# LinTempCont_4ch_V1_0.net
KiCad netlist of a schematic drawn in EAGLE
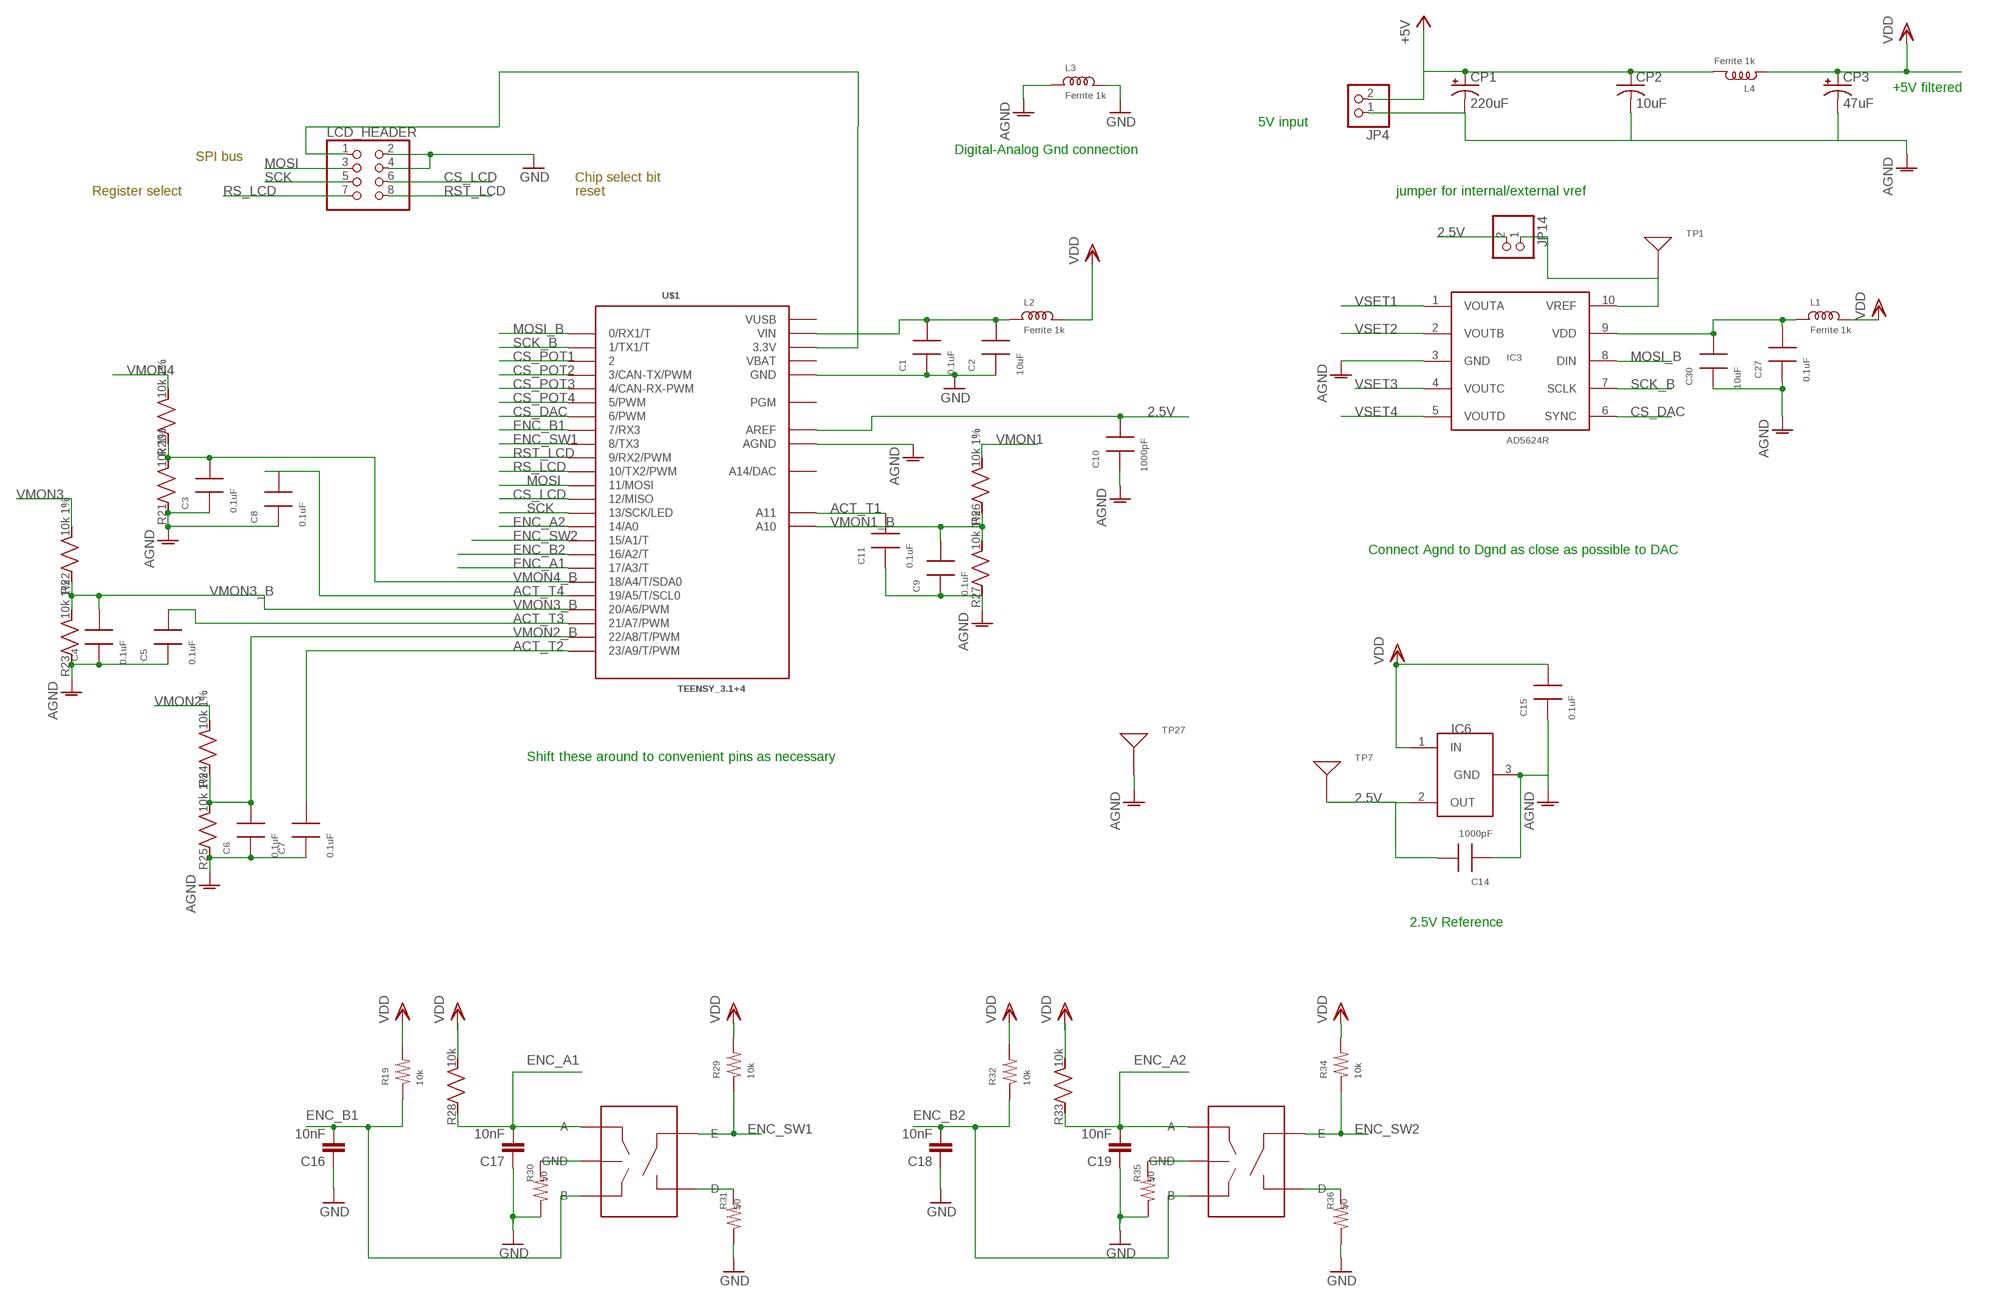
[diagram p0: schematic, sheet 1]
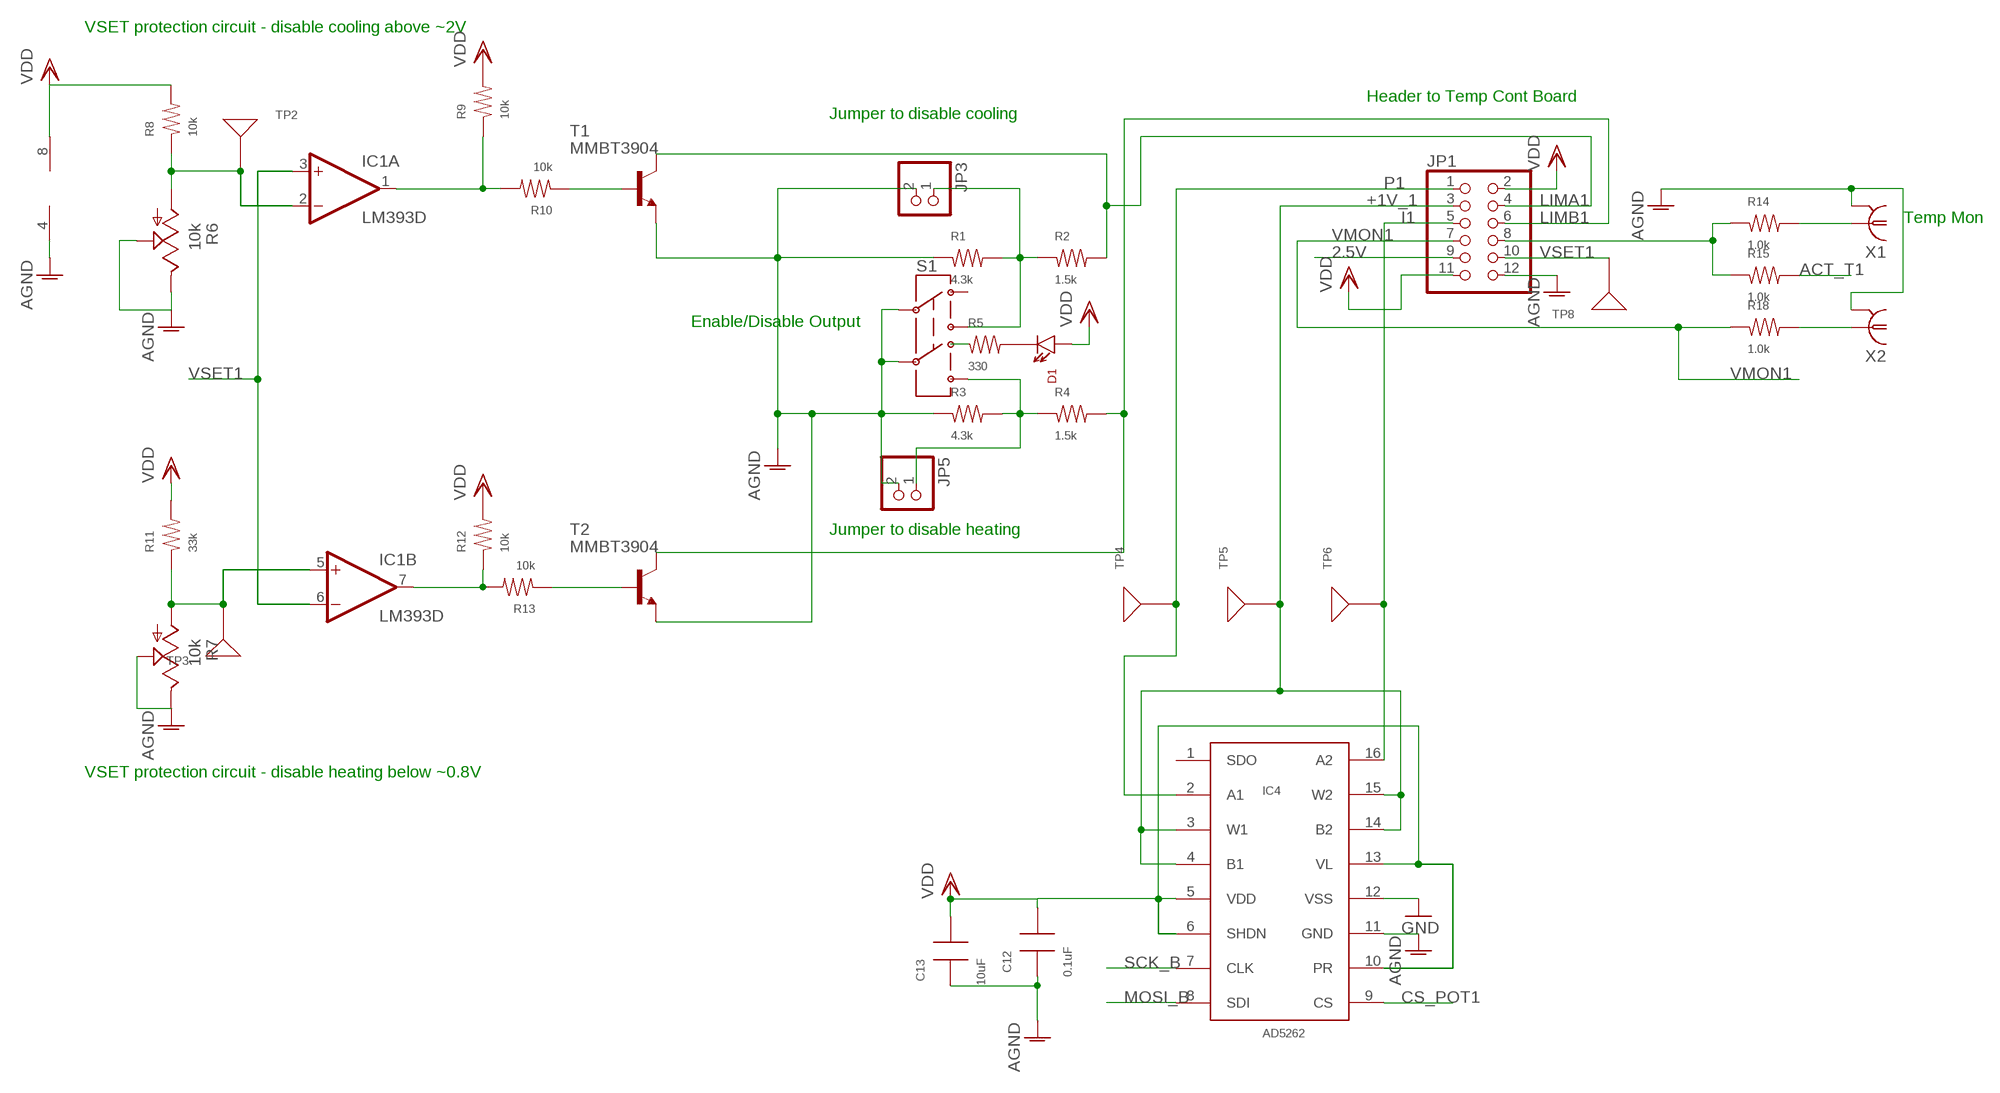
[diagram p1: schematic, sheet 2]
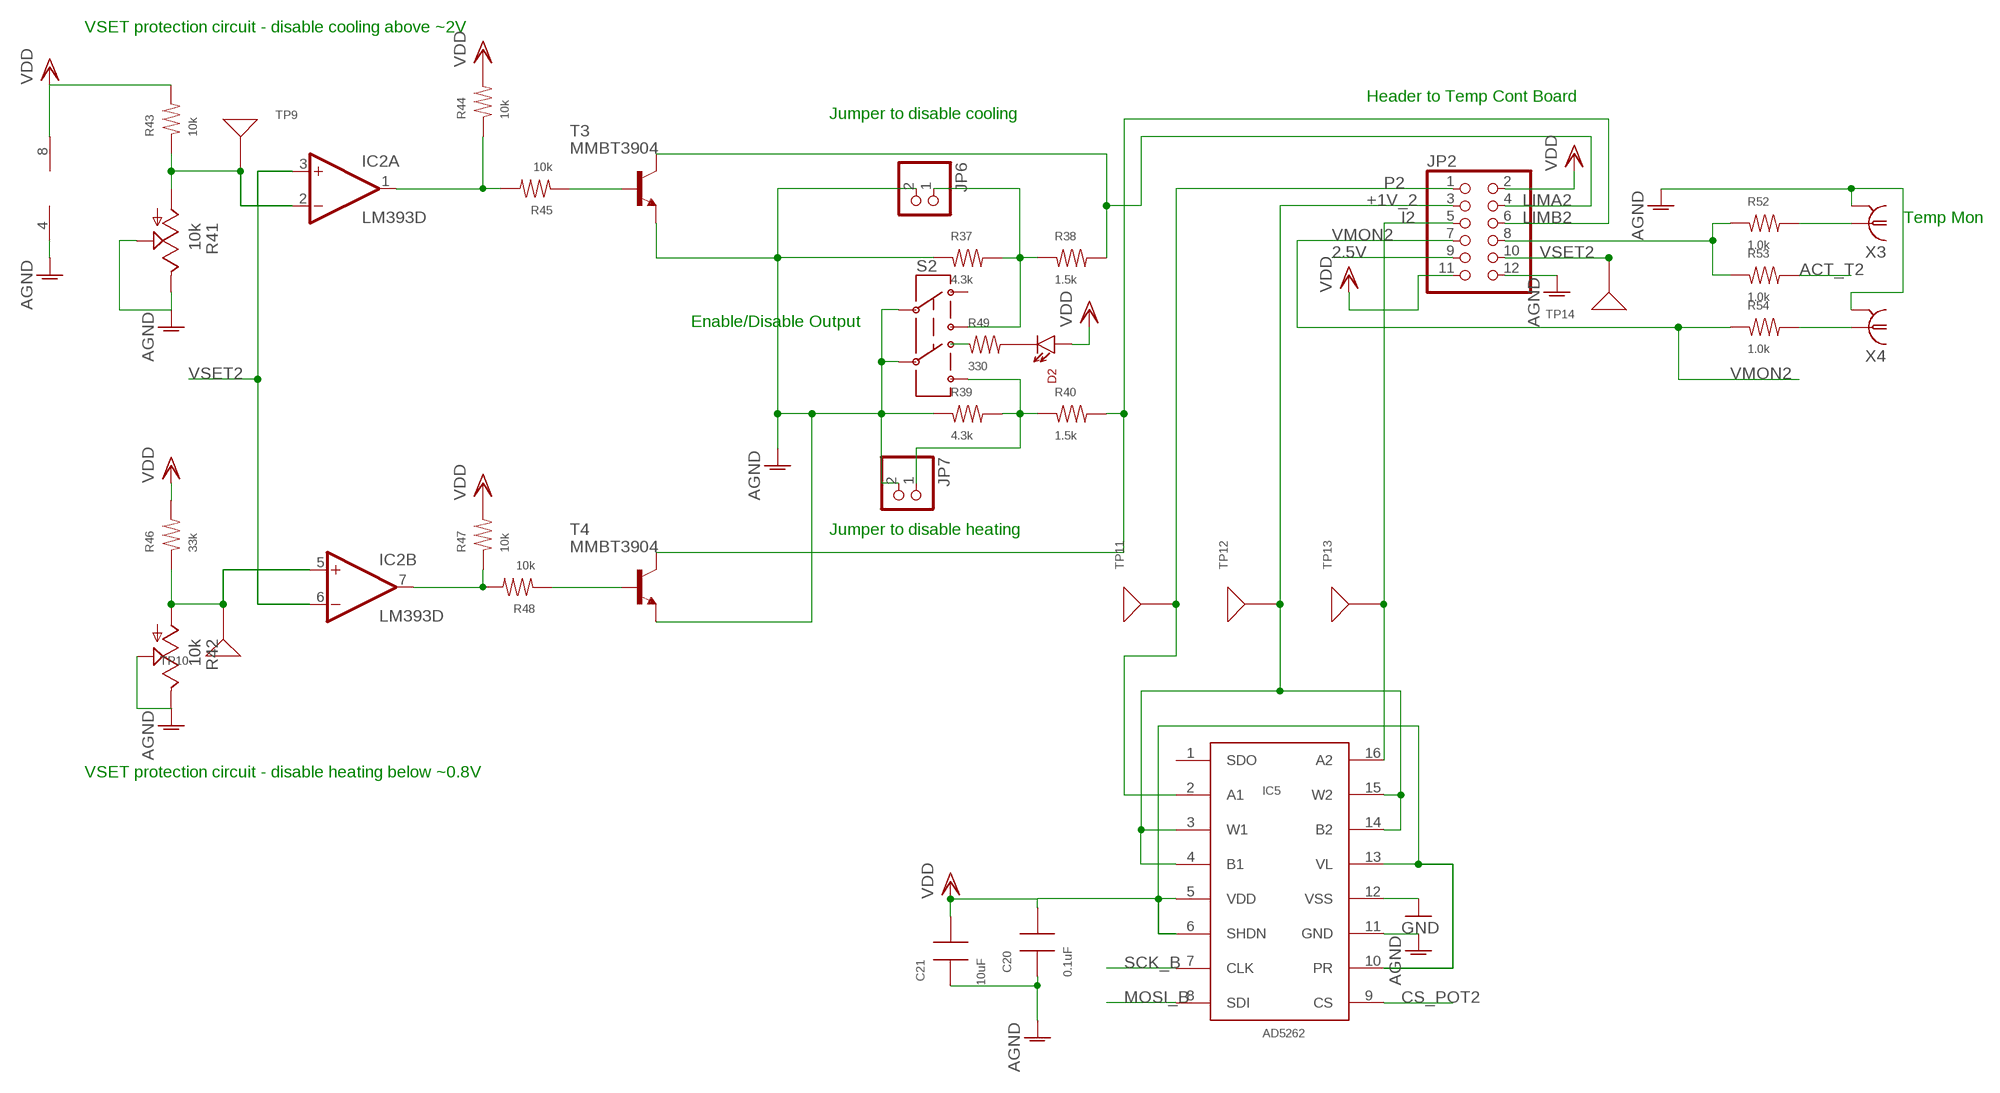
[diagram p2: schematic, sheet 3]
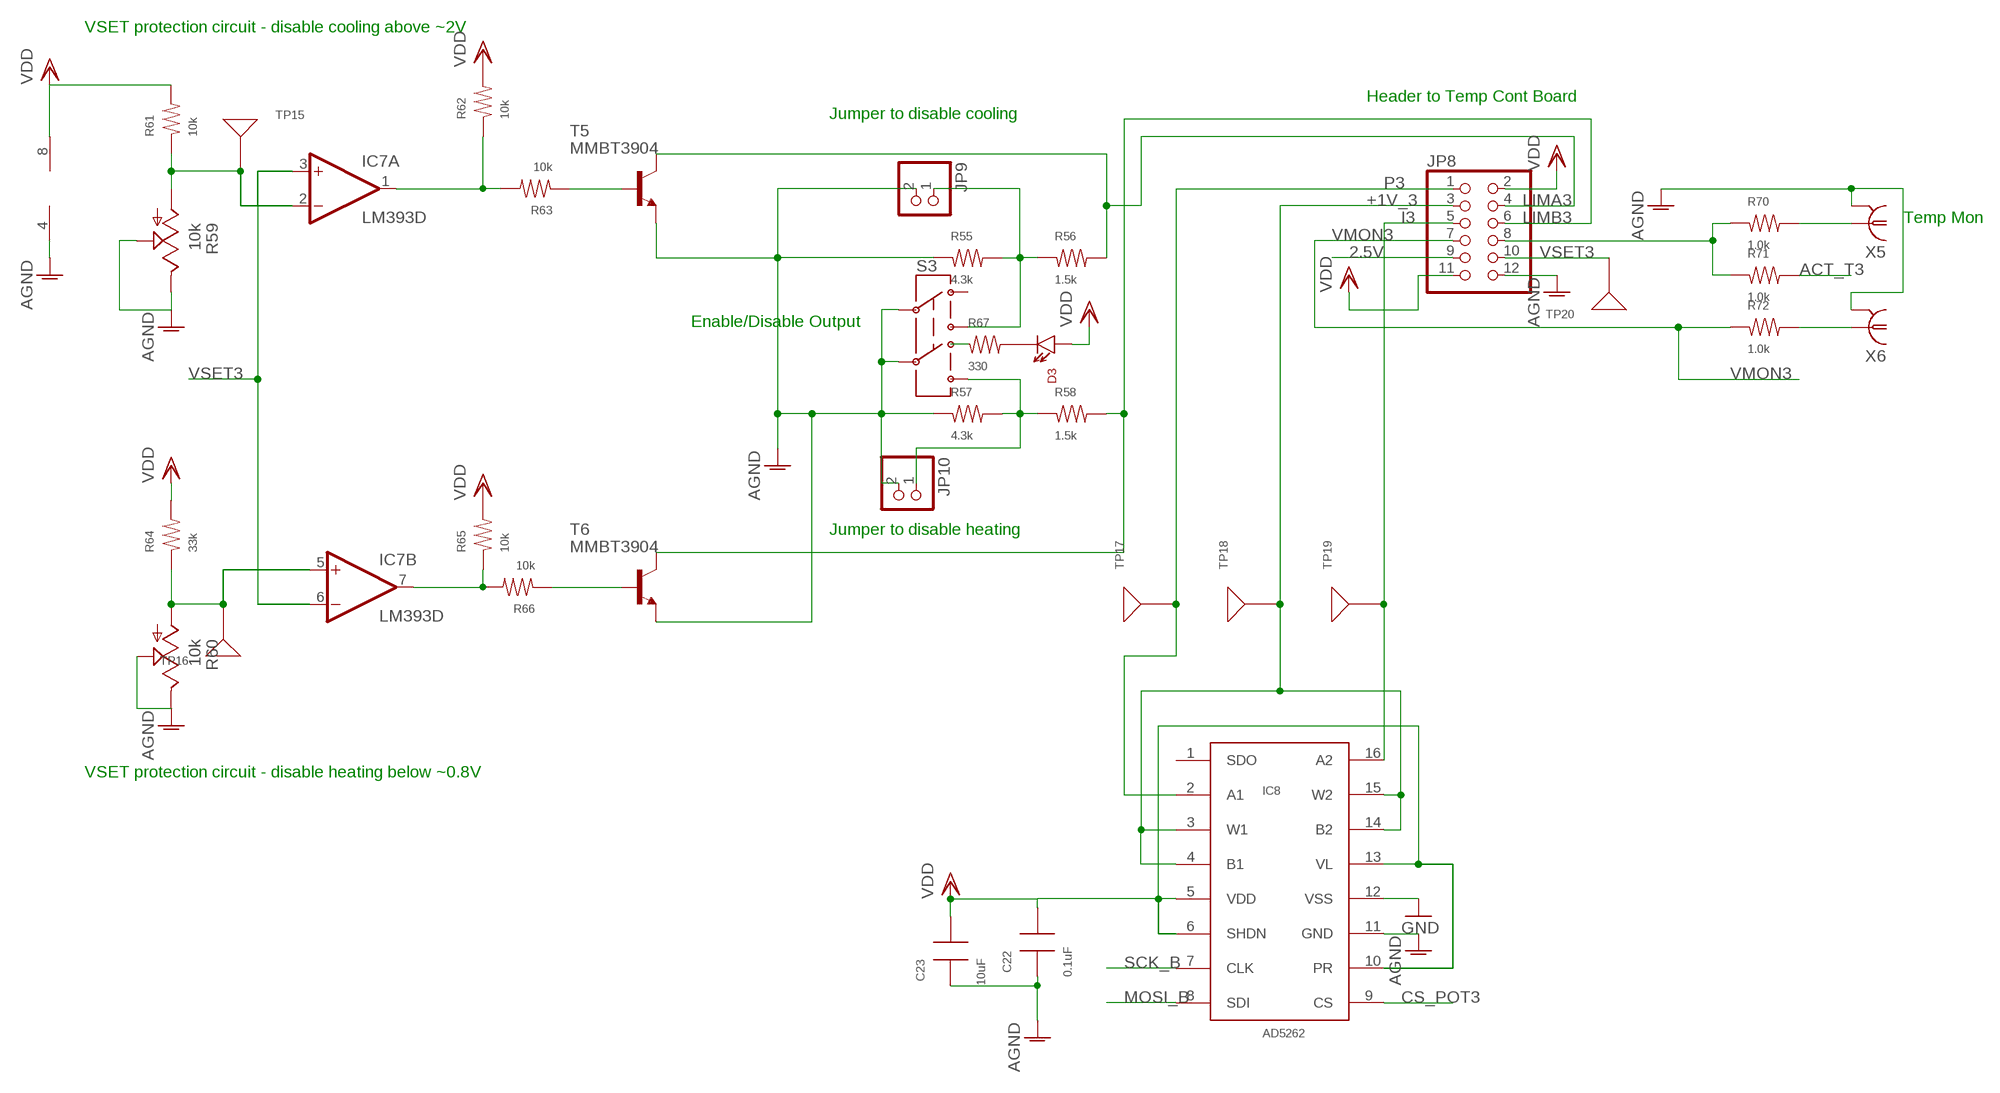
[diagram p3: schematic, sheet 4]
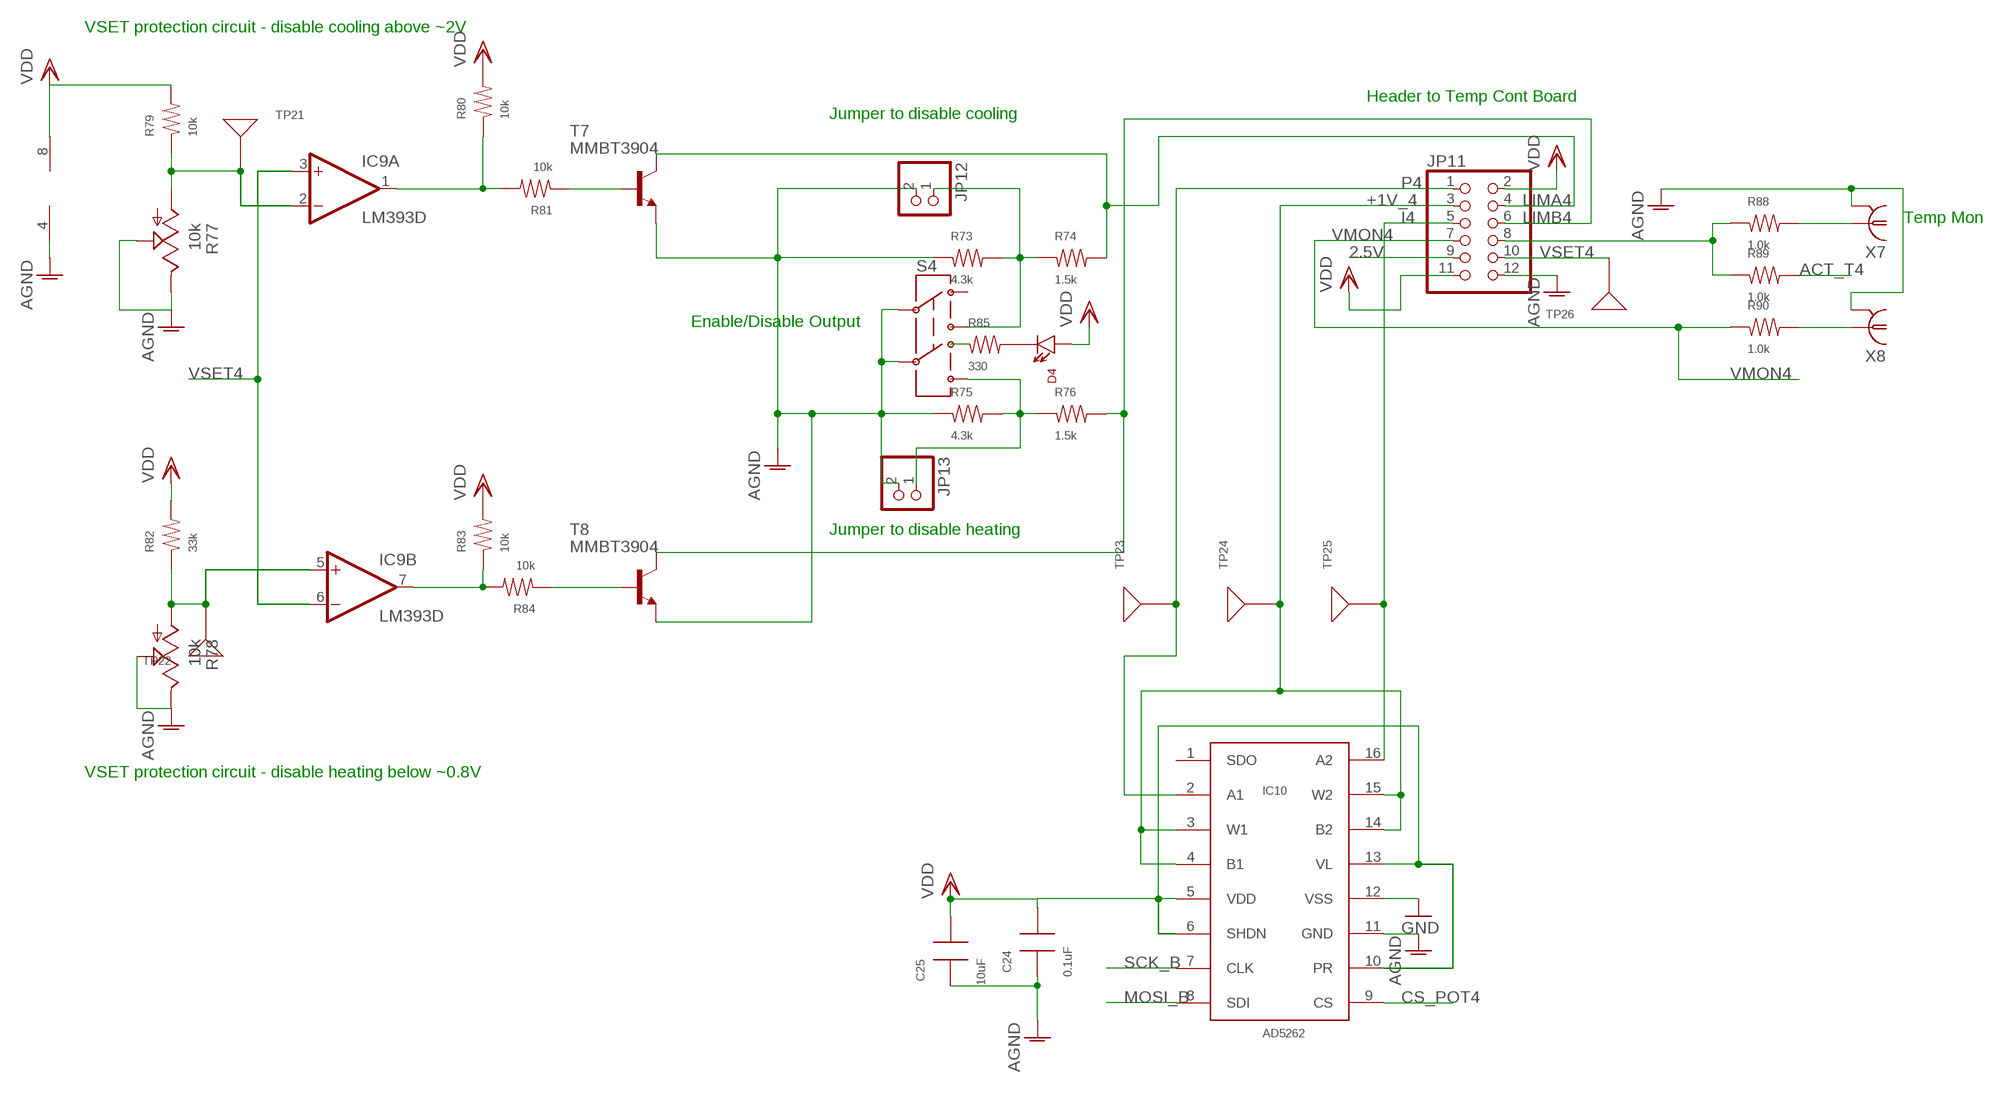
[diagram p4: schematic, sheet 5]

(export (version "E")
  (design (tool "Eeschema 10.0.6"))
  (components
    (comp (ref "C24")
      (value "0.1uF")
      (footprint "eagle-import:0603")
      (libsource (lib "eagle-import") (part "CAP0603"))
    )
    (comp (ref "C25")
      (value "10uF")
      (footprint "eagle-import:0805")
      (libsource (lib "eagle-import") (part "CAP0805"))
    )
    (comp (ref "D4")
      (value "LED/MINI-IND")
      (footprint "eagle-import:HLMP--F0010")
      (libsource (lib "eagle-import") (part "LED/MINI-IND"))
    )
    (comp (ref "IC9")
      (value "LM393D")
      (footprint "eagle-import:SO08")
      (libsource (lib "eagle-import") (part "LM393D"))
    )
    (comp (ref "IC10")
      (value "AD5262")
      (footprint "eagle-import:TSSOP16")
      (libsource (lib "eagle-import") (part "AD5262"))
    )
    (comp (ref "JP11")
      (value "PINHD-2X6/90")
      (footprint "eagle-import:2X06_90")
      (libsource (lib "eagle-import") (part "PINHD-2X6/90"))
    )
    (comp (ref "JP12")
      (value "PINHD-1X2")
      (footprint "eagle-import:1X02")
      (libsource (lib "eagle-import") (part "PINHD-1X2"))
    )
    (comp (ref "JP13")
      (value "PINHD-1X2")
      (footprint "eagle-import:1X02")
      (libsource (lib "eagle-import") (part "PINHD-1X2"))
    )
    (comp (ref "R73")
      (value "4.3k")
      (footprint "eagle-import:0603")
      (libsource (lib "eagle-import") (part "RES0603"))
    )
    (comp (ref "R74")
      (value "1.5k")
      (footprint "eagle-import:0603")
      (libsource (lib "eagle-import") (part "RES0603"))
    )
    (comp (ref "R75")
      (value "4.3k")
      (footprint "eagle-import:0603")
      (libsource (lib "eagle-import") (part "RES0603"))
    )
    (comp (ref "R76")
      (value "1.5k")
      (footprint "eagle-import:0603")
      (libsource (lib "eagle-import") (part "RES0603"))
    )
    (comp (ref "R77")
      (value "10k")
      (footprint "eagle-import:64WPOT")
      (libsource (lib "eagle-import") (part "MODEL64_TRIMPOT/TOP-ADJ"))
    )
    (comp (ref "R78")
      (value "10k")
      (footprint "eagle-import:64WPOT")
      (libsource (lib "eagle-import") (part "MODEL64_TRIMPOT/TOP-ADJ"))
    )
    (comp (ref "R79")
      (value "10k")
      (footprint "eagle-import:0603")
      (libsource (lib "eagle-import") (part "RES0603"))
    )
    (comp (ref "R80")
      (value "10k")
      (footprint "eagle-import:0603")
      (libsource (lib "eagle-import") (part "RES0603"))
    )
    (comp (ref "R81")
      (value "10k")
      (footprint "eagle-import:0603")
      (libsource (lib "eagle-import") (part "RES0603"))
    )
    (comp (ref "R82")
      (value "33k")
      (footprint "eagle-import:0603")
      (libsource (lib "eagle-import") (part "RES0603"))
    )
    (comp (ref "R83")
      (value "10k")
      (footprint "eagle-import:0603")
      (libsource (lib "eagle-import") (part "RES0603"))
    )
    (comp (ref "R84")
      (value "10k")
      (footprint "eagle-import:0603")
      (libsource (lib "eagle-import") (part "RES0603"))
    )
    (comp (ref "R85")
      (value "330")
      (footprint "eagle-import:0603")
      (libsource (lib "eagle-import") (part "RES0603"))
    )
    (comp (ref "R88")
      (value "1.0k")
      (footprint "eagle-import:0603")
      (libsource (lib "eagle-import") (part "RES0603"))
    )
    (comp (ref "R89")
      (value "1.0k")
      (footprint "eagle-import:0603")
      (libsource (lib "eagle-import") (part "RES0603"))
    )
    (comp (ref "R90")
      (value "1.0k")
      (footprint "eagle-import:0603")
      (libsource (lib "eagle-import") (part "RES0603"))
    )
    (comp (ref "S4")
      (value "SWITCH-DPDT/VER")
      (footprint "eagle-import:E-SWITCH-100-M7")
      (libsource (lib "eagle-import") (part "SWITCH-DPDT/VER"))
    )
    (comp (ref "T7")
      (value "MMBT3904")
      (footprint "eagle-import:SOT-23")
      (libsource (lib "eagle-import") (part "MMBT3904"))
    )
    (comp (ref "T8")
      (value "MMBT3904")
      (footprint "eagle-import:SOT-23")
      (libsource (lib "eagle-import") (part "MMBT3904"))
    )
    (comp (ref "TP21")
      (value "TESTPT")
      (footprint "eagle-import:1206TESTPAD")
      (libsource (lib "eagle-import") (part "TESTPT"))
    )
    (comp (ref "TP22")
      (value "TESTPT")
      (footprint "eagle-import:1206TESTPAD")
      (libsource (lib "eagle-import") (part "TESTPT"))
    )
    (comp (ref "TP23")
      (value "TESTPT")
      (footprint "eagle-import:1206TESTPAD")
      (libsource (lib "eagle-import") (part "TESTPT"))
    )
    (comp (ref "TP24")
      (value "TESTPT")
      (footprint "eagle-import:1206TESTPAD")
      (libsource (lib "eagle-import") (part "TESTPT"))
    )
    (comp (ref "TP25")
      (value "TESTPT")
      (footprint "eagle-import:1206TESTPAD")
      (libsource (lib "eagle-import") (part "TESTPT"))
    )
    (comp (ref "TP26")
      (value "TESTPT")
      (footprint "eagle-import:1206TESTPAD")
      (libsource (lib "eagle-import") (part "TESTPT"))
    )
    (comp (ref "X7")
      (value "BNC-H")
      (footprint "eagle-import:BNC90")
      (libsource (lib "eagle-import") (part "BNC-H"))
    )
    (comp (ref "X8")
      (value "BNC-H")
      (footprint "eagle-import:BNC90")
      (libsource (lib "eagle-import") (part "BNC-H"))
    )
    (comp (ref "C20")
      (value "0.1uF")
      (footprint "eagle-import:0603")
      (libsource (lib "eagle-import") (part "CAP0603"))
    )
    (comp (ref "C21")
      (value "10uF")
      (footprint "eagle-import:0805")
      (libsource (lib "eagle-import") (part "CAP0805"))
    )
    (comp (ref "D2")
      (value "LED/MINI-IND")
      (footprint "eagle-import:HLMP--F0010")
      (libsource (lib "eagle-import") (part "LED/MINI-IND"))
    )
    (comp (ref "IC2")
      (value "LM393D")
      (footprint "eagle-import:SO08")
      (libsource (lib "eagle-import") (part "LM393D"))
    )
    (comp (ref "IC5")
      (value "AD5262")
      (footprint "eagle-import:TSSOP16")
      (libsource (lib "eagle-import") (part "AD5262"))
    )
    (comp (ref "JP2")
      (value "PINHD-2X6/90")
      (footprint "eagle-import:2X06_90")
      (libsource (lib "eagle-import") (part "PINHD-2X6/90"))
    )
    (comp (ref "JP6")
      (value "PINHD-1X2")
      (footprint "eagle-import:1X02")
      (libsource (lib "eagle-import") (part "PINHD-1X2"))
    )
    (comp (ref "JP7")
      (value "PINHD-1X2")
      (footprint "eagle-import:1X02")
      (libsource (lib "eagle-import") (part "PINHD-1X2"))
    )
    (comp (ref "R37")
      (value "4.3k")
      (footprint "eagle-import:0603")
      (libsource (lib "eagle-import") (part "RES0603"))
    )
    (comp (ref "R38")
      (value "1.5k")
      (footprint "eagle-import:0603")
      (libsource (lib "eagle-import") (part "RES0603"))
    )
    (comp (ref "R39")
      (value "4.3k")
      (footprint "eagle-import:0603")
      (libsource (lib "eagle-import") (part "RES0603"))
    )
    (comp (ref "R40")
      (value "1.5k")
      (footprint "eagle-import:0603")
      (libsource (lib "eagle-import") (part "RES0603"))
    )
    (comp (ref "R41")
      (value "10k")
      (footprint "eagle-import:64WPOT")
      (libsource (lib "eagle-import") (part "MODEL64_TRIMPOT/TOP-ADJ"))
    )
    (comp (ref "R42")
      (value "10k")
      (footprint "eagle-import:64WPOT")
      (libsource (lib "eagle-import") (part "MODEL64_TRIMPOT/TOP-ADJ"))
    )
    (comp (ref "R43")
      (value "10k")
      (footprint "eagle-import:0603")
      (libsource (lib "eagle-import") (part "RES0603"))
    )
    (comp (ref "R44")
      (value "10k")
      (footprint "eagle-import:0603")
      (libsource (lib "eagle-import") (part "RES0603"))
    )
    (comp (ref "R45")
      (value "10k")
      (footprint "eagle-import:0603")
      (libsource (lib "eagle-import") (part "RES0603"))
    )
    (comp (ref "R46")
      (value "33k")
      (footprint "eagle-import:0603")
      (libsource (lib "eagle-import") (part "RES0603"))
    )
    (comp (ref "R47")
      (value "10k")
      (footprint "eagle-import:0603")
      (libsource (lib "eagle-import") (part "RES0603"))
    )
    (comp (ref "R48")
      (value "10k")
      (footprint "eagle-import:0603")
      (libsource (lib "eagle-import") (part "RES0603"))
    )
    (comp (ref "R49")
      (value "330")
      (footprint "eagle-import:0603")
      (libsource (lib "eagle-import") (part "RES0603"))
    )
    (comp (ref "R52")
      (value "1.0k")
      (footprint "eagle-import:0603")
      (libsource (lib "eagle-import") (part "RES0603"))
    )
    (comp (ref "R53")
      (value "1.0k")
      (footprint "eagle-import:0603")
      (libsource (lib "eagle-import") (part "RES0603"))
    )
    (comp (ref "R54")
      (value "1.0k")
      (footprint "eagle-import:0603")
      (libsource (lib "eagle-import") (part "RES0603"))
    )
    (comp (ref "S2")
      (value "SWITCH-DPDT/VER")
      (footprint "eagle-import:E-SWITCH-100-M7")
      (libsource (lib "eagle-import") (part "SWITCH-DPDT/VER"))
    )
    (comp (ref "T3")
      (value "MMBT3904")
      (footprint "eagle-import:SOT-23")
      (libsource (lib "eagle-import") (part "MMBT3904"))
    )
    (comp (ref "T4")
      (value "MMBT3904")
      (footprint "eagle-import:SOT-23")
      (libsource (lib "eagle-import") (part "MMBT3904"))
    )
    (comp (ref "TP9")
      (value "TESTPT")
      (footprint "eagle-import:1206TESTPAD")
      (libsource (lib "eagle-import") (part "TESTPT"))
    )
    (comp (ref "TP10")
      (value "TESTPT")
      (footprint "eagle-import:1206TESTPAD")
      (libsource (lib "eagle-import") (part "TESTPT"))
    )
    (comp (ref "TP11")
      (value "TESTPT")
      (footprint "eagle-import:1206TESTPAD")
      (libsource (lib "eagle-import") (part "TESTPT"))
    )
    (comp (ref "TP12")
      (value "TESTPT")
      (footprint "eagle-import:1206TESTPAD")
      (libsource (lib "eagle-import") (part "TESTPT"))
    )
    (comp (ref "TP13")
      (value "TESTPT")
      (footprint "eagle-import:1206TESTPAD")
      (libsource (lib "eagle-import") (part "TESTPT"))
    )
    (comp (ref "TP14")
      (value "TESTPT")
      (footprint "eagle-import:1206TESTPAD")
      (libsource (lib "eagle-import") (part "TESTPT"))
    )
    (comp (ref "X3")
      (value "BNC-H")
      (footprint "eagle-import:BNC90")
      (libsource (lib "eagle-import") (part "BNC-H"))
    )
    (comp (ref "X4")
      (value "BNC-H")
      (footprint "eagle-import:BNC90")
      (libsource (lib "eagle-import") (part "BNC-H"))
    )
    (comp (ref "C12")
      (value "0.1uF")
      (footprint "eagle-import:0603")
      (libsource (lib "eagle-import") (part "CAP0603"))
    )
    (comp (ref "C13")
      (value "10uF")
      (footprint "eagle-import:0805")
      (libsource (lib "eagle-import") (part "CAP0805"))
    )
    (comp (ref "D1")
      (value "LED/MINI-IND")
      (footprint "eagle-import:HLMP--F0010")
      (libsource (lib "eagle-import") (part "LED/MINI-IND"))
    )
    (comp (ref "IC1")
      (value "LM393D")
      (footprint "eagle-import:SO08")
      (libsource (lib "eagle-import") (part "LM393D"))
    )
    (comp (ref "IC4")
      (value "AD5262")
      (footprint "eagle-import:TSSOP16")
      (libsource (lib "eagle-import") (part "AD5262"))
    )
    (comp (ref "JP1")
      (value "PINHD-2X6/90")
      (footprint "eagle-import:2X06_90")
      (libsource (lib "eagle-import") (part "PINHD-2X6/90"))
    )
    (comp (ref "JP3")
      (value "PINHD-1X2")
      (footprint "eagle-import:1X02")
      (libsource (lib "eagle-import") (part "PINHD-1X2"))
    )
    (comp (ref "JP5")
      (value "PINHD-1X2")
      (footprint "eagle-import:1X02")
      (libsource (lib "eagle-import") (part "PINHD-1X2"))
    )
    (comp (ref "R1")
      (value "4.3k")
      (footprint "eagle-import:0603")
      (libsource (lib "eagle-import") (part "RES0603"))
    )
    (comp (ref "R2")
      (value "1.5k")
      (footprint "eagle-import:0603")
      (libsource (lib "eagle-import") (part "RES0603"))
    )
    (comp (ref "R3")
      (value "4.3k")
      (footprint "eagle-import:0603")
      (libsource (lib "eagle-import") (part "RES0603"))
    )
    (comp (ref "R4")
      (value "1.5k")
      (footprint "eagle-import:0603")
      (libsource (lib "eagle-import") (part "RES0603"))
    )
    (comp (ref "R5")
      (value "330")
      (footprint "eagle-import:0603")
      (libsource (lib "eagle-import") (part "RES0603"))
    )
    (comp (ref "R6")
      (value "10k")
      (footprint "eagle-import:64WPOT")
      (libsource (lib "eagle-import") (part "MODEL64_TRIMPOT/TOP-ADJ"))
    )
    (comp (ref "R7")
      (value "10k")
      (footprint "eagle-import:64WPOT")
      (libsource (lib "eagle-import") (part "MODEL64_TRIMPOT/TOP-ADJ"))
    )
    (comp (ref "R8")
      (value "10k")
      (footprint "eagle-import:0603")
      (libsource (lib "eagle-import") (part "RES0603"))
    )
    (comp (ref "R9")
      (value "10k")
      (footprint "eagle-import:0603")
      (libsource (lib "eagle-import") (part "RES0603"))
    )
    (comp (ref "R10")
      (value "10k")
      (footprint "eagle-import:0603")
      (libsource (lib "eagle-import") (part "RES0603"))
    )
    (comp (ref "R11")
      (value "33k")
      (footprint "eagle-import:0603")
      (libsource (lib "eagle-import") (part "RES0603"))
    )
    (comp (ref "R12")
      (value "10k")
      (footprint "eagle-import:0603")
      (libsource (lib "eagle-import") (part "RES0603"))
    )
    (comp (ref "R13")
      (value "10k")
      (footprint "eagle-import:0603")
      (libsource (lib "eagle-import") (part "RES0603"))
    )
    (comp (ref "R14")
      (value "1.0k")
      (footprint "eagle-import:0603")
      (libsource (lib "eagle-import") (part "RES0603"))
    )
    (comp (ref "R15")
      (value "1.0k")
      (footprint "eagle-import:0603")
      (libsource (lib "eagle-import") (part "RES0603"))
    )
    (comp (ref "R18")
      (value "1.0k")
      (footprint "eagle-import:0603")
      (libsource (lib "eagle-import") (part "RES0603"))
    )
    (comp (ref "S1")
      (value "SWITCH-DPDT/VER")
      (footprint "eagle-import:E-SWITCH-100-M7")
      (libsource (lib "eagle-import") (part "SWITCH-DPDT/VER"))
    )
    (comp (ref "T1")
      (value "MMBT3904")
      (footprint "eagle-import:SOT-23")
      (libsource (lib "eagle-import") (part "MMBT3904"))
    )
    (comp (ref "T2")
      (value "MMBT3904")
      (footprint "eagle-import:SOT-23")
      (libsource (lib "eagle-import") (part "MMBT3904"))
    )
    (comp (ref "TP2")
      (value "TESTPT")
      (footprint "eagle-import:1206TESTPAD")
      (libsource (lib "eagle-import") (part "TESTPT"))
    )
    (comp (ref "TP3")
      (value "TESTPT")
      (footprint "eagle-import:1206TESTPAD")
      (libsource (lib "eagle-import") (part "TESTPT"))
    )
    (comp (ref "TP4")
      (value "TESTPT")
      (footprint "eagle-import:1206TESTPAD")
      (libsource (lib "eagle-import") (part "TESTPT"))
    )
    (comp (ref "TP5")
      (value "TESTPT")
      (footprint "eagle-import:1206TESTPAD")
      (libsource (lib "eagle-import") (part "TESTPT"))
    )
    (comp (ref "TP6")
      (value "TESTPT")
      (footprint "eagle-import:1206TESTPAD")
      (libsource (lib "eagle-import") (part "TESTPT"))
    )
    (comp (ref "TP8")
      (value "TESTPT")
      (footprint "eagle-import:1206TESTPAD")
      (libsource (lib "eagle-import") (part "TESTPT"))
    )
    (comp (ref "X1")
      (value "BNC-H")
      (footprint "eagle-import:BNC90")
      (libsource (lib "eagle-import") (part "BNC-H"))
    )
    (comp (ref "X2")
      (value "BNC-H")
      (footprint "eagle-import:BNC90")
      (libsource (lib "eagle-import") (part "BNC-H"))
    )
    (comp (ref "C1")
      (value "0.1uF")
      (footprint "eagle-import:0603")
      (libsource (lib "eagle-import") (part "CAP0603"))
    )
    (comp (ref "C2")
      (value "10uF")
      (footprint "eagle-import:0805")
      (libsource (lib "eagle-import") (part "CAP0805"))
    )
    (comp (ref "C3")
      (value "0.1uF")
      (footprint "eagle-import:0603")
      (libsource (lib "eagle-import") (part "CAP0603"))
    )
    (comp (ref "C4")
      (value "0.1uF")
      (footprint "eagle-import:0603")
      (libsource (lib "eagle-import") (part "CAP0603"))
    )
    (comp (ref "C5")
      (value "0.1uF")
      (footprint "eagle-import:0603")
      (libsource (lib "eagle-import") (part "CAP0603"))
    )
    (comp (ref "C6")
      (value "0.1uF")
      (footprint "eagle-import:0603")
      (libsource (lib "eagle-import") (part "CAP0603"))
    )
    (comp (ref "C7")
      (value "0.1uF")
      (footprint "eagle-import:0603")
      (libsource (lib "eagle-import") (part "CAP0603"))
    )
    (comp (ref "C8")
      (value "0.1uF")
      (footprint "eagle-import:0603")
      (libsource (lib "eagle-import") (part "CAP0603"))
    )
    (comp (ref "C9")
      (value "0.1uF")
      (footprint "eagle-import:0603")
      (libsource (lib "eagle-import") (part "CAP0603"))
    )
    (comp (ref "C10")
      (value "1000pF")
      (footprint "eagle-import:0603")
      (libsource (lib "eagle-import") (part "CAP0603"))
    )
    (comp (ref "C11")
      (value "0.1uF")
      (footprint "eagle-import:0603")
      (libsource (lib "eagle-import") (part "CAP0603"))
    )
    (comp (ref "C14")
      (value "1000pF")
      (footprint "eagle-import:0603")
      (libsource (lib "eagle-import") (part "CAP0603"))
    )
    (comp (ref "C15")
      (value "0.1uF")
      (footprint "eagle-import:0603")
      (libsource (lib "eagle-import") (part "CAP0603"))
    )
    (comp (ref "C16")
      (value "10nF")
      (footprint "eagle-import:C0603")
      (libsource (lib "eagle-import") (part "C-EUC0603"))
    )
    (comp (ref "C17")
      (value "10nF")
      (footprint "eagle-import:C0603")
      (libsource (lib "eagle-import") (part "C-EUC0603"))
    )
    (comp (ref "C18")
      (value "10nF")
      (footprint "eagle-import:C0603")
      (libsource (lib "eagle-import") (part "C-EUC0603"))
    )
    (comp (ref "C19")
      (value "10nF")
      (footprint "eagle-import:C0603")
      (libsource (lib "eagle-import") (part "C-EUC0603"))
    )
    (comp (ref "C27")
      (value "0.1uF")
      (footprint "eagle-import:0603")
      (libsource (lib "eagle-import") (part "CAP0603"))
    )
    (comp (ref "C30")
      (value "10uF")
      (footprint "eagle-import:0805")
      (libsource (lib "eagle-import") (part "CAP0805"))
    )
    (comp (ref "CP1")
      (value "220uF")
      (footprint "eagle-import:PANASONIC_F")
      (libsource (lib "eagle-import") (part "CPOL-USF"))
    )
    (comp (ref "CP2")
      (value "10uF")
      (footprint "eagle-import:C0805K")
      (libsource (lib "eagle-import") (part "C-USC0805K"))
    )
    (comp (ref "CP3")
      (value "47uF")
      (footprint "eagle-import:CT7343")
      (libsource (lib "eagle-import") (part "CPOL-USCT7343"))
    )
    (comp (ref "ENC1")
      (value "PEC09")
      (footprint "eagle-import:PEC092320FS")
      (libsource (lib "eagle-import") (part "PEC09"))
    )
    (comp (ref "ENC2")
      (value "PEC09")
      (footprint "eagle-import:PEC092320FS")
      (libsource (lib "eagle-import") (part "PEC09"))
    )
    (comp (ref "IC3")
      (value "AD5624R")
      (footprint "eagle-import:MSOP10")
      (libsource (lib "eagle-import") (part "AD5624R"))
    )
    (comp (ref "IC6")
      (value "TS6001")
      (footprint "eagle-import:SOT-23")
      (libsource (lib "eagle-import") (part "TS6001"))
    )
    (comp (ref "JP4")
      (value "SCRWTRM-1X2")
      (footprint "eagle-import:1X02_SCRWTRM")
      (libsource (lib "eagle-import") (part "SCRWTRM-1X2"))
    )
    (comp (ref "JP14")
      (value "PINHD-1X2")
      (footprint "eagle-import:1X02")
      (libsource (lib "eagle-import") (part "PINHD-1X2"))
    )
    (comp (ref "L1")
      (value "Ferrite 1k")
      (footprint "eagle-import:0805")
      (libsource (lib "eagle-import") (part "INDUCTOR-0805"))
    )
    (comp (ref "L2")
      (value "Ferrite 1k")
      (footprint "eagle-import:0805")
      (libsource (lib "eagle-import") (part "INDUCTOR-0805"))
    )
    (comp (ref "L3")
      (value "Ferrite 1k")
      (footprint "eagle-import:0805")
      (libsource (lib "eagle-import") (part "INDUCTOR-0805"))
    )
    (comp (ref "L4")
      (value "Ferrite 1k")
      (footprint "eagle-import:0805")
      (libsource (lib "eagle-import") (part "INDUCTOR-0805"))
    )
    (comp (ref "LCD_HEADER")
      (value "PINHD-2X4-SHROUD")
      (footprint "eagle-import:ML08")
      (libsource (lib "eagle-import") (part "PINHD-2X4-SHROUD"))
    )
    (comp (ref "R19")
      (value "10k")
      (footprint "eagle-import:0603")
      (libsource (lib "eagle-import") (part "RES0603"))
    )
    (comp (ref "R20")
      (value "10k 1%")
      (footprint "eagle-import:R_0603")
      (libsource (lib "eagle-import") (part "R_SMDR0603"))
    )
    (comp (ref "R21")
      (value "10k 1%")
      (footprint "eagle-import:R_0603")
      (libsource (lib "eagle-import") (part "R_SMDR0603"))
    )
    (comp (ref "R22")
      (value "10k 1%")
      (footprint "eagle-import:R_0603")
      (libsource (lib "eagle-import") (part "R_SMDR0603"))
    )
    (comp (ref "R23")
      (value "10k 1%")
      (footprint "eagle-import:R_0603")
      (libsource (lib "eagle-import") (part "R_SMDR0603"))
    )
    (comp (ref "R24")
      (value "10k 1%")
      (footprint "eagle-import:R_0603")
      (libsource (lib "eagle-import") (part "R_SMDR0603"))
    )
    (comp (ref "R25")
      (value "10k 1%")
      (footprint "eagle-import:R_0603")
      (libsource (lib "eagle-import") (part "R_SMDR0603"))
    )
    (comp (ref "R26")
      (value "10k 1%")
      (footprint "eagle-import:R_0603")
      (libsource (lib "eagle-import") (part "R_SMDR0603"))
    )
    (comp (ref "R27")
      (value "10k 1%")
      (footprint "eagle-import:R_0603")
      (libsource (lib "eagle-import") (part "R_SMDR0603"))
    )
    (comp (ref "R28")
      (value "10k")
      (footprint "eagle-import:R_0603")
      (libsource (lib "eagle-import") (part "R_SMDR0603"))
    )
    (comp (ref "R29")
      (value "10k")
      (footprint "eagle-import:0603")
      (libsource (lib "eagle-import") (part "RES0603"))
    )
    (comp (ref "R30")
      (value "50")
      (footprint "eagle-import:0603")
      (libsource (lib "eagle-import") (part "RES0603"))
    )
    (comp (ref "R31")
      (value "50")
      (footprint "eagle-import:0603")
      (libsource (lib "eagle-import") (part "RES0603"))
    )
    (comp (ref "R32")
      (value "10k")
      (footprint "eagle-import:0603")
      (libsource (lib "eagle-import") (part "RES0603"))
    )
    (comp (ref "R33")
      (value "10k")
      (footprint "eagle-import:R_0603")
      (libsource (lib "eagle-import") (part "R_SMDR0603"))
    )
    (comp (ref "R34")
      (value "10k")
      (footprint "eagle-import:0603")
      (libsource (lib "eagle-import") (part "RES0603"))
    )
    (comp (ref "R35")
      (value "50")
      (footprint "eagle-import:0603")
      (libsource (lib "eagle-import") (part "RES0603"))
    )
    (comp (ref "R36")
      (value "50")
      (footprint "eagle-import:0603")
      (libsource (lib "eagle-import") (part "RES0603"))
    )
    (comp (ref "TP1")
      (value "TESTPT")
      (footprint "eagle-import:1206TESTPAD")
      (libsource (lib "eagle-import") (part "TESTPT"))
    )
    (comp (ref "TP7")
      (value "TESTPT")
      (footprint "eagle-import:1206TESTPAD")
      (libsource (lib "eagle-import") (part "TESTPT"))
    )
    (comp (ref "TP27")
      (value "TESTPT")
      (footprint "eagle-import:1206TESTPAD")
      (libsource (lib "eagle-import") (part "TESTPT"))
    )
    (comp (ref "U$1")
      (value "TEENSY_3.1+4")
      (footprint "eagle-import:TEENSY_3.1+4")
      (libsource (lib "eagle-import") (part "TEENSY_3.1+4"))
    )
    (comp (ref "C22")
      (value "0.1uF")
      (footprint "eagle-import:0603")
      (libsource (lib "eagle-import") (part "CAP0603"))
    )
    (comp (ref "C23")
      (value "10uF")
      (footprint "eagle-import:0805")
      (libsource (lib "eagle-import") (part "CAP0805"))
    )
    (comp (ref "D3")
      (value "LED/MINI-IND")
      (footprint "eagle-import:HLMP--F0010")
      (libsource (lib "eagle-import") (part "LED/MINI-IND"))
    )
    (comp (ref "IC7")
      (value "LM393D")
      (footprint "eagle-import:SO08")
      (libsource (lib "eagle-import") (part "LM393D"))
    )
    (comp (ref "IC8")
      (value "AD5262")
      (footprint "eagle-import:TSSOP16")
      (libsource (lib "eagle-import") (part "AD5262"))
    )
    (comp (ref "JP8")
      (value "PINHD-2X6/90")
      (footprint "eagle-import:2X06_90")
      (libsource (lib "eagle-import") (part "PINHD-2X6/90"))
    )
    (comp (ref "JP9")
      (value "PINHD-1X2")
      (footprint "eagle-import:1X02")
      (libsource (lib "eagle-import") (part "PINHD-1X2"))
    )
    (comp (ref "JP10")
      (value "PINHD-1X2")
      (footprint "eagle-import:1X02")
      (libsource (lib "eagle-import") (part "PINHD-1X2"))
    )
    (comp (ref "R55")
      (value "4.3k")
      (footprint "eagle-import:0603")
      (libsource (lib "eagle-import") (part "RES0603"))
    )
    (comp (ref "R56")
      (value "1.5k")
      (footprint "eagle-import:0603")
      (libsource (lib "eagle-import") (part "RES0603"))
    )
    (comp (ref "R57")
      (value "4.3k")
      (footprint "eagle-import:0603")
      (libsource (lib "eagle-import") (part "RES0603"))
    )
    (comp (ref "R58")
      (value "1.5k")
      (footprint "eagle-import:0603")
      (libsource (lib "eagle-import") (part "RES0603"))
    )
    (comp (ref "R59")
      (value "10k")
      (footprint "eagle-import:64WPOT")
      (libsource (lib "eagle-import") (part "MODEL64_TRIMPOT/TOP-ADJ"))
    )
    (comp (ref "R60")
      (value "10k")
      (footprint "eagle-import:64WPOT")
      (libsource (lib "eagle-import") (part "MODEL64_TRIMPOT/TOP-ADJ"))
    )
    (comp (ref "R61")
      (value "10k")
      (footprint "eagle-import:0603")
      (libsource (lib "eagle-import") (part "RES0603"))
    )
    (comp (ref "R62")
      (value "10k")
      (footprint "eagle-import:0603")
      (libsource (lib "eagle-import") (part "RES0603"))
    )
    (comp (ref "R63")
      (value "10k")
      (footprint "eagle-import:0603")
      (libsource (lib "eagle-import") (part "RES0603"))
    )
    (comp (ref "R64")
      (value "33k")
      (footprint "eagle-import:0603")
      (libsource (lib "eagle-import") (part "RES0603"))
    )
    (comp (ref "R65")
      (value "10k")
      (footprint "eagle-import:0603")
      (libsource (lib "eagle-import") (part "RES0603"))
    )
    (comp (ref "R66")
      (value "10k")
      (footprint "eagle-import:0603")
      (libsource (lib "eagle-import") (part "RES0603"))
    )
    (comp (ref "R67")
      (value "330")
      (footprint "eagle-import:0603")
      (libsource (lib "eagle-import") (part "RES0603"))
    )
    (comp (ref "R70")
      (value "1.0k")
      (footprint "eagle-import:0603")
      (libsource (lib "eagle-import") (part "RES0603"))
    )
    (comp (ref "R71")
      (value "1.0k")
      (footprint "eagle-import:0603")
      (libsource (lib "eagle-import") (part "RES0603"))
    )
    (comp (ref "R72")
      (value "1.0k")
      (footprint "eagle-import:0603")
      (libsource (lib "eagle-import") (part "RES0603"))
    )
    (comp (ref "S3")
      (value "SWITCH-DPDT/VER")
      (footprint "eagle-import:E-SWITCH-100-M7")
      (libsource (lib "eagle-import") (part "SWITCH-DPDT/VER"))
    )
    (comp (ref "T5")
      (value "MMBT3904")
      (footprint "eagle-import:SOT-23")
      (libsource (lib "eagle-import") (part "MMBT3904"))
    )
    (comp (ref "T6")
      (value "MMBT3904")
      (footprint "eagle-import:SOT-23")
      (libsource (lib "eagle-import") (part "MMBT3904"))
    )
    (comp (ref "TP15")
      (value "TESTPT")
      (footprint "eagle-import:1206TESTPAD")
      (libsource (lib "eagle-import") (part "TESTPT"))
    )
    (comp (ref "TP16")
      (value "TESTPT")
      (footprint "eagle-import:1206TESTPAD")
      (libsource (lib "eagle-import") (part "TESTPT"))
    )
    (comp (ref "TP17")
      (value "TESTPT")
      (footprint "eagle-import:1206TESTPAD")
      (libsource (lib "eagle-import") (part "TESTPT"))
    )
    (comp (ref "TP18")
      (value "TESTPT")
      (footprint "eagle-import:1206TESTPAD")
      (libsource (lib "eagle-import") (part "TESTPT"))
    )
    (comp (ref "TP19")
      (value "TESTPT")
      (footprint "eagle-import:1206TESTPAD")
      (libsource (lib "eagle-import") (part "TESTPT"))
    )
    (comp (ref "TP20")
      (value "TESTPT")
      (footprint "eagle-import:1206TESTPAD")
      (libsource (lib "eagle-import") (part "TESTPT"))
    )
    (comp (ref "X5")
      (value "BNC-H")
      (footprint "eagle-import:BNC90")
      (libsource (lib "eagle-import") (part "BNC-H"))
    )
    (comp (ref "X6")
      (value "BNC-H")
      (footprint "eagle-import:BNC90")
      (libsource (lib "eagle-import") (part "BNC-H"))
    )
  )
  (nets
    (net (code "1") (name "+1V_1") (class "Default")
      (node (ref "IC4") (pin "14") (pinfunction "B2_14") (pintype "bidirectional"))
      (node (ref "IC4") (pin "15") (pinfunction "W2_15") (pintype "bidirectional"))
      (node (ref "IC4") (pin "3") (pinfunction "W1_3") (pintype "bidirectional"))
      (node (ref "IC4") (pin "4") (pinfunction "B1_4") (pintype "bidirectional"))
      (node (ref "JP1") (pin "3") (pinfunction "3_3") (pintype "passive"))
      (node (ref "TP5") (pin "P$1") (pinfunction "P$1_P$1") (pintype "bidirectional"))
    )
    (net (code "2") (name "+1V_2") (class "Default")
      (node (ref "IC5") (pin "14") (pinfunction "B2_14") (pintype "bidirectional"))
      (node (ref "IC5") (pin "15") (pinfunction "W2_15") (pintype "bidirectional"))
      (node (ref "IC5") (pin "3") (pinfunction "W1_3") (pintype "bidirectional"))
      (node (ref "IC5") (pin "4") (pinfunction "B1_4") (pintype "bidirectional"))
      (node (ref "JP2") (pin "3") (pinfunction "3_3") (pintype "passive"))
      (node (ref "TP12") (pin "P$1") (pinfunction "P$1_P$1") (pintype "bidirectional"))
    )
    (net (code "3") (name "+1V_3") (class "Default")
      (node (ref "IC8") (pin "14") (pinfunction "B2_14") (pintype "bidirectional"))
      (node (ref "IC8") (pin "15") (pinfunction "W2_15") (pintype "bidirectional"))
      (node (ref "IC8") (pin "3") (pinfunction "W1_3") (pintype "bidirectional"))
      (node (ref "IC8") (pin "4") (pinfunction "B1_4") (pintype "bidirectional"))
      (node (ref "JP8") (pin "3") (pinfunction "3_3") (pintype "passive"))
      (node (ref "TP18") (pin "P$1") (pinfunction "P$1_P$1") (pintype "bidirectional"))
    )
    (net (code "4") (name "+1V_4") (class "Default")
      (node (ref "IC10") (pin "14") (pinfunction "B2_14") (pintype "bidirectional"))
      (node (ref "IC10") (pin "15") (pinfunction "W2_15") (pintype "bidirectional"))
      (node (ref "IC10") (pin "3") (pinfunction "W1_3") (pintype "bidirectional"))
      (node (ref "IC10") (pin "4") (pinfunction "B1_4") (pintype "bidirectional"))
      (node (ref "JP11") (pin "3") (pinfunction "3_3") (pintype "passive"))
      (node (ref "TP24") (pin "P$1") (pinfunction "P$1_P$1") (pintype "bidirectional"))
    )
    (net (code "5") (name "+5V") (class "Default")
      (node (ref "CP1") (pin "+") (pinfunction "+_+") (pintype "passive"))
      (node (ref "CP2") (pin "1") (pinfunction "1_1") (pintype "passive"))
      (node (ref "JP4") (pin "2") (pinfunction "2_2") (pintype "passive"))
      (node (ref "L4") (pin "2") (pinfunction "P$2_2") (pintype "passive"))
    )
    (net (code "6") (name "2.5V") (class "Default")
      (node (ref "C10") (pin "2") (pinfunction "P$2_2") (pintype "passive"))
      (node (ref "C14") (pin "2") (pinfunction "P$2_2") (pintype "passive"))
      (node (ref "IC6") (pin "2") (pinfunction "OUT_2") (pintype "bidirectional"))
      (node (ref "JP1") (pin "9") (pinfunction "9_9") (pintype "passive"))
      (node (ref "JP11") (pin "9") (pinfunction "9_9") (pintype "passive"))
      (node (ref "JP14") (pin "2") (pinfunction "2_2") (pintype "passive"))
      (node (ref "JP2") (pin "9") (pinfunction "9_9") (pintype "passive"))
      (node (ref "JP8") (pin "9") (pinfunction "9_9") (pintype "passive"))
      (node (ref "TP7") (pin "P$1") (pinfunction "P$1_P$1") (pintype "bidirectional"))
      (node (ref "U$1") (pin "AREF") (pinfunction "AREF_AREF") (pintype "power_in"))
    )
    (net (code "7") (name "ACT_T1") (class "Default")
      (node (ref "C11") (pin "2") (pinfunction "P$2_2") (pintype "passive"))
      (node (ref "R15") (pin "2") (pinfunction "P$2_2") (pintype "passive"))
      (node (ref "U$1") (pin "A11") (pinfunction "A11_A11") (pintype "bidirectional"))
    )
    (net (code "8") (name "ACT_T2") (class "Default")
      (node (ref "C7") (pin "2") (pinfunction "P$2_2") (pintype "passive"))
      (node (ref "R53") (pin "2") (pinfunction "P$2_2") (pintype "passive"))
      (node (ref "U$1") (pin "23/A9") (pinfunction "23/A9/T/PWM_23/A9") (pintype "bidirectional"))
    )
    (net (code "9") (name "ACT_T3") (class "Default")
      (node (ref "C5") (pin "2") (pinfunction "P$2_2") (pintype "passive"))
      (node (ref "R71") (pin "2") (pinfunction "P$2_2") (pintype "passive"))
      (node (ref "U$1") (pin "21/A7") (pinfunction "21/A7/PWM_21/A7") (pintype "bidirectional"))
    )
    (net (code "10") (name "ACT_T4") (class "Default")
      (node (ref "C8") (pin "2") (pinfunction "P$2_2") (pintype "passive"))
      (node (ref "R89") (pin "2") (pinfunction "P$2_2") (pintype "passive"))
      (node (ref "U$1") (pin "19/A5") (pinfunction "19/A5/T/SCL0_19/A5") (pintype "bidirectional"))
    )
    (net (code "11") (name "AGND") (class "Default")
      (node (ref "C10") (pin "1") (pinfunction "P$1_1") (pintype "passive"))
      (node (ref "C11") (pin "1") (pinfunction "P$1_1") (pintype "passive"))
      (node (ref "C12") (pin "1") (pinfunction "P$1_1") (pintype "passive"))
      (node (ref "C13") (pin "1") (pinfunction "P$1_1") (pintype "passive"))
      (node (ref "C14") (pin "1") (pinfunction "P$1_1") (pintype "passive"))
      (node (ref "C15") (pin "1") (pinfunction "P$1_1") (pintype "passive"))
      (node (ref "C20") (pin "1") (pinfunction "P$1_1") (pintype "passive"))
      (node (ref "C21") (pin "1") (pinfunction "P$1_1") (pintype "passive"))
      (node (ref "C22") (pin "1") (pinfunction "P$1_1") (pintype "passive"))
      (node (ref "C23") (pin "1") (pinfunction "P$1_1") (pintype "passive"))
      (node (ref "C24") (pin "1") (pinfunction "P$1_1") (pintype "passive"))
      (node (ref "C25") (pin "1") (pinfunction "P$1_1") (pintype "passive"))
      (node (ref "C27") (pin "1") (pinfunction "P$1_1") (pintype "passive"))
      (node (ref "C3") (pin "1") (pinfunction "P$1_1") (pintype "passive"))
      (node (ref "C30") (pin "1") (pinfunction "P$1_1") (pintype "passive"))
      (node (ref "C4") (pin "1") (pinfunction "P$1_1") (pintype "passive"))
      (node (ref "C5") (pin "1") (pinfunction "P$1_1") (pintype "passive"))
      (node (ref "C6") (pin "1") (pinfunction "P$1_1") (pintype "passive"))
      (node (ref "C7") (pin "1") (pinfunction "P$1_1") (pintype "passive"))
      (node (ref "C8") (pin "1") (pinfunction "P$1_1") (pintype "passive"))
      (node (ref "C9") (pin "1") (pinfunction "P$1_1") (pintype "passive"))
      (node (ref "CP1") (pin "-") (pinfunction "-_-") (pintype "passive"))
      (node (ref "CP2") (pin "2") (pinfunction "2_2") (pintype "passive"))
      (node (ref "CP3") (pin "-") (pinfunction "-_-") (pintype "passive"))
      (node (ref "IC1") (pin "4") (pinfunction "V-_4") (pintype "power_in"))
      (node (ref "IC10") (pin "11") (pinfunction "GND_11") (pintype "power_in"))
      (node (ref "IC2") (pin "4") (pinfunction "V-_4") (pintype "power_in"))
      (node (ref "IC3") (pin "3") (pinfunction "GND_3") (pintype "power_in"))
      (node (ref "IC4") (pin "11") (pinfunction "GND_11") (pintype "power_in"))
      (node (ref "IC5") (pin "11") (pinfunction "GND_11") (pintype "power_in"))
      (node (ref "IC6") (pin "3") (pinfunction "GND_3") (pintype "bidirectional"))
      (node (ref "IC7") (pin "4") (pinfunction "V-_4") (pintype "power_in"))
      (node (ref "IC8") (pin "11") (pinfunction "GND_11") (pintype "power_in"))
      (node (ref "IC9") (pin "4") (pinfunction "V-_4") (pintype "power_in"))
      (node (ref "JP1") (pin "12") (pinfunction "12_12") (pintype "passive"))
      (node (ref "JP10") (pin "2") (pinfunction "2_2") (pintype "passive"))
      (node (ref "JP11") (pin "12") (pinfunction "12_12") (pintype "passive"))
      (node (ref "JP12") (pin "2") (pinfunction "2_2") (pintype "passive"))
      (node (ref "JP13") (pin "2") (pinfunction "2_2") (pintype "passive"))
      (node (ref "JP2") (pin "12") (pinfunction "12_12") (pintype "passive"))
      (node (ref "JP3") (pin "2") (pinfunction "2_2") (pintype "passive"))
      (node (ref "JP4") (pin "1") (pinfunction "1_1") (pintype "passive"))
      (node (ref "JP5") (pin "2") (pinfunction "2_2") (pintype "passive"))
      (node (ref "JP6") (pin "2") (pinfunction "2_2") (pintype "passive"))
      (node (ref "JP7") (pin "2") (pinfunction "2_2") (pintype "passive"))
      (node (ref "JP8") (pin "12") (pinfunction "12_12") (pintype "passive"))
      (node (ref "JP9") (pin "2") (pinfunction "2_2") (pintype "passive"))
      (node (ref "L3") (pin "1") (pinfunction "P$1_1") (pintype "passive"))
      (node (ref "R1") (pin "1") (pinfunction "P$1_1") (pintype "passive"))
      (node (ref "R21") (pin "P$1") (pinfunction "1_P$1") (pintype "passive"))
      (node (ref "R23") (pin "P$1") (pinfunction "1_P$1") (pintype "passive"))
      (node (ref "R25") (pin "P$1") (pinfunction "1_P$1") (pintype "passive"))
      (node (ref "R27") (pin "P$1") (pinfunction "1_P$1") (pintype "passive"))
      (node (ref "R3") (pin "1") (pinfunction "P$1_1") (pintype "passive"))
      (node (ref "R37") (pin "1") (pinfunction "P$1_1") (pintype "passive"))
      (node (ref "R39") (pin "1") (pinfunction "P$1_1") (pintype "passive"))
      (node (ref "R41") (pin "P$2") (pinfunction "2_P$2") (pintype "passive"))
      (node (ref "R41") (pin "P$3") (pinfunction "3_P$3") (pintype "passive"))
      (node (ref "R42") (pin "P$2") (pinfunction "2_P$2") (pintype "passive"))
      (node (ref "R42") (pin "P$3") (pinfunction "3_P$3") (pintype "passive"))
      (node (ref "R55") (pin "1") (pinfunction "P$1_1") (pintype "passive"))
      (node (ref "R57") (pin "1") (pinfunction "P$1_1") (pintype "passive"))
      (node (ref "R59") (pin "P$2") (pinfunction "2_P$2") (pintype "passive"))
      (node (ref "R59") (pin "P$3") (pinfunction "3_P$3") (pintype "passive"))
      (node (ref "R6") (pin "P$2") (pinfunction "2_P$2") (pintype "passive"))
      (node (ref "R6") (pin "P$3") (pinfunction "3_P$3") (pintype "passive"))
      (node (ref "R60") (pin "P$2") (pinfunction "2_P$2") (pintype "passive"))
      (node (ref "R60") (pin "P$3") (pinfunction "3_P$3") (pintype "passive"))
      (node (ref "R7") (pin "P$2") (pinfunction "2_P$2") (pintype "passive"))
      (node (ref "R7") (pin "P$3") (pinfunction "3_P$3") (pintype "passive"))
      (node (ref "R73") (pin "1") (pinfunction "P$1_1") (pintype "passive"))
      (node (ref "R75") (pin "1") (pinfunction "P$1_1") (pintype "passive"))
      (node (ref "R77") (pin "P$2") (pinfunction "2_P$2") (pintype "passive"))
      (node (ref "R77") (pin "P$3") (pinfunction "3_P$3") (pintype "passive"))
      (node (ref "R78") (pin "P$2") (pinfunction "2_P$2") (pintype "passive"))
      (node (ref "R78") (pin "P$3") (pinfunction "3_P$3") (pintype "passive"))
      (node (ref "S1") (pin "P$2") (pinfunction "2_P$2") (pintype "bidirectional"))
      (node (ref "S1") (pin "P$5") (pinfunction "5_P$5") (pintype "bidirectional"))
      (node (ref "S2") (pin "P$2") (pinfunction "2_P$2") (pintype "bidirectional"))
      (node (ref "S2") (pin "P$5") (pinfunction "5_P$5") (pintype "bidirectional"))
      (node (ref "S3") (pin "P$2") (pinfunction "2_P$2") (pintype "bidirectional"))
      (node (ref "S3") (pin "P$5") (pinfunction "5_P$5") (pintype "bidirectional"))
      (node (ref "S4") (pin "P$2") (pinfunction "2_P$2") (pintype "bidirectional"))
      (node (ref "S4") (pin "P$5") (pinfunction "5_P$5") (pintype "bidirectional"))
      (node (ref "T1") (pin "2") (pinfunction "E_2") (pintype "passive"))
      (node (ref "T2") (pin "2") (pinfunction "E_2") (pintype "passive"))
      (node (ref "T3") (pin "2") (pinfunction "E_2") (pintype "passive"))
      (node (ref "T4") (pin "2") (pinfunction "E_2") (pintype "passive"))
      (node (ref "T5") (pin "2") (pinfunction "E_2") (pintype "passive"))
      (node (ref "T6") (pin "2") (pinfunction "E_2") (pintype "passive"))
      (node (ref "T7") (pin "2") (pinfunction "E_2") (pintype "passive"))
      (node (ref "T8") (pin "2") (pinfunction "E_2") (pintype "passive"))
      (node (ref "TP27") (pin "P$1") (pinfunction "P$1_P$1") (pintype "bidirectional"))
      (node (ref "U$1") (pin "AGND") (pinfunction "AGND_AGND") (pintype "power_in"))
      (node (ref "X1") (pin "2") (pinfunction "2_2") (pintype "passive"))
      (node (ref "X2") (pin "2") (pinfunction "2_2") (pintype "passive"))
      (node (ref "X3") (pin "2") (pinfunction "2_2") (pintype "passive"))
      (node (ref "X4") (pin "2") (pinfunction "2_2") (pintype "passive"))
      (node (ref "X5") (pin "2") (pinfunction "2_2") (pintype "passive"))
      (node (ref "X6") (pin "2") (pinfunction "2_2") (pintype "passive"))
      (node (ref "X7") (pin "2") (pinfunction "2_2") (pintype "passive"))
      (node (ref "X8") (pin "2") (pinfunction "2_2") (pintype "passive"))
    )
    (net (code "12") (name "CS_DAC") (class "Default")
      (node (ref "IC3") (pin "6") (pinfunction "SYNC_6") (pintype "bidirectional"))
      (node (ref "U$1") (pin "6") (pinfunction "6/PWM_6") (pintype "bidirectional"))
    )
    (net (code "13") (name "CS_LCD") (class "Default")
      (node (ref "LCD_HEADER") (pin "6") (pinfunction "6_6") (pintype "passive"))
      (node (ref "U$1") (pin "12") (pinfunction "12/MISO_12") (pintype "bidirectional"))
    )
    (net (code "14") (name "CS_POT1") (class "Default")
      (node (ref "IC4") (pin "9") (pinfunction "CS_9") (pintype "bidirectional"))
      (node (ref "U$1") (pin "2") (pinfunction "2_2") (pintype "bidirectional"))
    )
    (net (code "15") (name "CS_POT2") (class "Default")
      (node (ref "IC5") (pin "9") (pinfunction "CS_9") (pintype "bidirectional"))
      (node (ref "U$1") (pin "3") (pinfunction "3/CAN-TX/PWM_3") (pintype "bidirectional"))
    )
    (net (code "16") (name "CS_POT3") (class "Default")
      (node (ref "IC8") (pin "9") (pinfunction "CS_9") (pintype "bidirectional"))
      (node (ref "U$1") (pin "4") (pinfunction "4/CAN-RX-PWM_4") (pintype "bidirectional"))
    )
    (net (code "17") (name "CS_POT4") (class "Default")
      (node (ref "IC10") (pin "9") (pinfunction "CS_9") (pintype "bidirectional"))
      (node (ref "U$1") (pin "5") (pinfunction "5/PWM_5") (pintype "bidirectional"))
    )
    (net (code "18") (name "ENC_A1") (class "Default")
      (node (ref "C17") (pin "2") (pinfunction "2_2") (pintype "passive"))
      (node (ref "ENC1") (pin "A") (pinfunction "A_A") (pintype "bidirectional"))
      (node (ref "R28") (pin "P$1") (pinfunction "1_P$1") (pintype "passive"))
      (node (ref "U$1") (pin "17/A3") (pinfunction "17/A3/T_17/A3") (pintype "bidirectional"))
    )
    (net (code "19") (name "ENC_A2") (class "Default")
      (node (ref "C19") (pin "2") (pinfunction "2_2") (pintype "passive"))
      (node (ref "ENC2") (pin "A") (pinfunction "A_A") (pintype "bidirectional"))
      (node (ref "R33") (pin "P$1") (pinfunction "1_P$1") (pintype "passive"))
      (node (ref "U$1") (pin "14/A0") (pinfunction "14/A0_14/A0") (pintype "bidirectional"))
    )
    (net (code "20") (name "ENC_B1") (class "Default")
      (node (ref "C16") (pin "2") (pinfunction "2_2") (pintype "passive"))
      (node (ref "ENC1") (pin "B") (pinfunction "B_B") (pintype "bidirectional"))
      (node (ref "R19") (pin "1") (pinfunction "P$1_1") (pintype "passive"))
      (node (ref "U$1") (pin "7") (pinfunction "7/RX3_7") (pintype "bidirectional"))
    )
    (net (code "21") (name "ENC_B2") (class "Default")
      (node (ref "C18") (pin "2") (pinfunction "2_2") (pintype "passive"))
      (node (ref "ENC2") (pin "B") (pinfunction "B_B") (pintype "bidirectional"))
      (node (ref "R32") (pin "1") (pinfunction "P$1_1") (pintype "passive"))
      (node (ref "U$1") (pin "16/A2") (pinfunction "16/A2/T_16/A2") (pintype "bidirectional"))
    )
    (net (code "22") (name "ENC_SW1") (class "Default")
      (node (ref "ENC1") (pin "E") (pinfunction "E_E") (pintype "bidirectional"))
      (node (ref "R29") (pin "1") (pinfunction "P$1_1") (pintype "passive"))
      (node (ref "U$1") (pin "8") (pinfunction "8/TX3_8") (pintype "bidirectional"))
    )
    (net (code "23") (name "ENC_SW2") (class "Default")
      (node (ref "ENC2") (pin "E") (pinfunction "E_E") (pintype "bidirectional"))
      (node (ref "R34") (pin "1") (pinfunction "P$1_1") (pintype "passive"))
      (node (ref "U$1") (pin "15/A1") (pinfunction "15/A1/T_15/A1") (pintype "bidirectional"))
    )
    (net (code "24") (name "GND") (class "Default")
      (node (ref "C1") (pin "1") (pinfunction "P$1_1") (pintype "passive"))
      (node (ref "C16") (pin "1") (pinfunction "1_1") (pintype "passive"))
      (node (ref "C17") (pin "1") (pinfunction "1_1") (pintype "passive"))
      (node (ref "C18") (pin "1") (pinfunction "1_1") (pintype "passive"))
      (node (ref "C19") (pin "1") (pinfunction "1_1") (pintype "passive"))
      (node (ref "C2") (pin "1") (pinfunction "P$1_1") (pintype "passive"))
      (node (ref "IC10") (pin "12") (pinfunction "VSS_12") (pintype "power_in"))
      (node (ref "IC4") (pin "12") (pinfunction "VSS_12") (pintype "power_in"))
      (node (ref "IC5") (pin "12") (pinfunction "VSS_12") (pintype "power_in"))
      (node (ref "IC8") (pin "12") (pinfunction "VSS_12") (pintype "power_in"))
      (node (ref "L3") (pin "2") (pinfunction "P$2_2") (pintype "passive"))
      (node (ref "LCD_HEADER") (pin "2") (pinfunction "2_2") (pintype "passive"))
      (node (ref "LCD_HEADER") (pin "4") (pinfunction "4_4") (pintype "passive"))
      (node (ref "R30") (pin "1") (pinfunction "P$1_1") (pintype "passive"))
      (node (ref "R31") (pin "1") (pinfunction "P$1_1") (pintype "passive"))
      (node (ref "R35") (pin "1") (pinfunction "P$1_1") (pintype "passive"))
      (node (ref "R36") (pin "1") (pinfunction "P$1_1") (pintype "passive"))
      (node (ref "U$1") (pin "GND") (pinfunction "GND_GND") (pintype "power_in"))
      (node (ref "U$1") (pin "GND1") (pinfunction "GND_GND1") (pintype "power_in"))
    )
    (net (code "25") (name "I1") (class "Default")
      (node (ref "IC4") (pin "16") (pinfunction "A2_16") (pintype "bidirectional"))
      (node (ref "JP1") (pin "5") (pinfunction "5_5") (pintype "passive"))
      (node (ref "TP6") (pin "P$1") (pinfunction "P$1_P$1") (pintype "bidirectional"))
    )
    (net (code "26") (name "I2") (class "Default")
      (node (ref "IC5") (pin "16") (pinfunction "A2_16") (pintype "bidirectional"))
      (node (ref "JP2") (pin "5") (pinfunction "5_5") (pintype "passive"))
      (node (ref "TP13") (pin "P$1") (pinfunction "P$1_P$1") (pintype "bidirectional"))
    )
    (net (code "27") (name "I3") (class "Default")
      (node (ref "IC8") (pin "16") (pinfunction "A2_16") (pintype "bidirectional"))
      (node (ref "JP8") (pin "5") (pinfunction "5_5") (pintype "passive"))
      (node (ref "TP19") (pin "P$1") (pinfunction "P$1_P$1") (pintype "bidirectional"))
    )
    (net (code "28") (name "I4") (class "Default")
      (node (ref "IC10") (pin "16") (pinfunction "A2_16") (pintype "bidirectional"))
      (node (ref "JP11") (pin "5") (pinfunction "5_5") (pintype "passive"))
      (node (ref "TP25") (pin "P$1") (pinfunction "P$1_P$1") (pintype "bidirectional"))
    )
    (net (code "29") (name "LIMA1") (class "Default")
      (node (ref "JP1") (pin "4") (pinfunction "4_4") (pintype "passive"))
      (node (ref "R2") (pin "2") (pinfunction "P$2_2") (pintype "passive"))
      (node (ref "T1") (pin "3") (pinfunction "C_3") (pintype "passive"))
    )
    (net (code "30") (name "LIMA2") (class "Default")
      (node (ref "JP2") (pin "4") (pinfunction "4_4") (pintype "passive"))
      (node (ref "R38") (pin "2") (pinfunction "P$2_2") (pintype "passive"))
      (node (ref "T3") (pin "3") (pinfunction "C_3") (pintype "passive"))
    )
    (net (code "31") (name "LIMA3") (class "Default")
      (node (ref "JP8") (pin "4") (pinfunction "4_4") (pintype "passive"))
      (node (ref "R56") (pin "2") (pinfunction "P$2_2") (pintype "passive"))
      (node (ref "T5") (pin "3") (pinfunction "C_3") (pintype "passive"))
    )
    (net (code "32") (name "LIMA4") (class "Default")
      (node (ref "JP11") (pin "4") (pinfunction "4_4") (pintype "passive"))
      (node (ref "R74") (pin "2") (pinfunction "P$2_2") (pintype "passive"))
      (node (ref "T7") (pin "3") (pinfunction "C_3") (pintype "passive"))
    )
    (net (code "33") (name "LIMB1") (class "Default")
      (node (ref "JP1") (pin "6") (pinfunction "6_6") (pintype "passive"))
      (node (ref "R4") (pin "2") (pinfunction "P$2_2") (pintype "passive"))
      (node (ref "T2") (pin "3") (pinfunction "C_3") (pintype "passive"))
    )
    (net (code "34") (name "LIMB2") (class "Default")
      (node (ref "JP2") (pin "6") (pinfunction "6_6") (pintype "passive"))
      (node (ref "R40") (pin "2") (pinfunction "P$2_2") (pintype "passive"))
      (node (ref "T4") (pin "3") (pinfunction "C_3") (pintype "passive"))
    )
    (net (code "35") (name "LIMB3") (class "Default")
      (node (ref "JP8") (pin "6") (pinfunction "6_6") (pintype "passive"))
      (node (ref "R58") (pin "2") (pinfunction "P$2_2") (pintype "passive"))
      (node (ref "T6") (pin "3") (pinfunction "C_3") (pintype "passive"))
    )
    (net (code "36") (name "LIMB4") (class "Default")
      (node (ref "JP11") (pin "6") (pinfunction "6_6") (pintype "passive"))
      (node (ref "R76") (pin "2") (pinfunction "P$2_2") (pintype "passive"))
      (node (ref "T8") (pin "3") (pinfunction "C_3") (pintype "passive"))
    )
    (net (code "37") (name "MOSI") (class "Default")
      (node (ref "LCD_HEADER") (pin "3") (pinfunction "3_3") (pintype "passive"))
      (node (ref "U$1") (pin "11") (pinfunction "11/MOSI_11") (pintype "bidirectional"))
    )
    (net (code "38") (name "MOSI_B") (class "Default")
      (node (ref "IC10") (pin "8") (pinfunction "SDI_8") (pintype "bidirectional"))
      (node (ref "IC3") (pin "8") (pinfunction "DIN_8") (pintype "bidirectional"))
      (node (ref "IC4") (pin "8") (pinfunction "SDI_8") (pintype "bidirectional"))
      (node (ref "IC5") (pin "8") (pinfunction "SDI_8") (pintype "bidirectional"))
      (node (ref "IC8") (pin "8") (pinfunction "SDI_8") (pintype "bidirectional"))
      (node (ref "U$1") (pin "0") (pinfunction "0/RX1/T_0") (pintype "bidirectional"))
    )
    (net (code "39") (name "Net-(C1-P$2)") (class "Default")
      (node (ref "C1") (pin "2") (pinfunction "P$2_2") (pintype "passive"))
      (node (ref "C2") (pin "2") (pinfunction "P$2_2") (pintype "passive"))
      (node (ref "L2") (pin "1") (pinfunction "P$1_1") (pintype "passive"))
      (node (ref "U$1") (pin "VIN") (pinfunction "VIN_VIN") (pintype "power_in"))
    )
    (net (code "40") (name "Net-(C27-P$2)") (class "Default")
      (node (ref "C27") (pin "2") (pinfunction "P$2_2") (pintype "passive"))
      (node (ref "C30") (pin "2") (pinfunction "P$2_2") (pintype "passive"))
      (node (ref "IC3") (pin "9") (pinfunction "VDD_9") (pintype "power_in"))
      (node (ref "L1") (pin "1") (pinfunction "P$1_1") (pintype "passive"))
    )
    (net (code "41") (name "Net-(ENC1-GND)") (class "Default")
      (node (ref "ENC1") (pin "C") (pinfunction "GND_C") (pintype "bidirectional"))
      (node (ref "R30") (pin "2") (pinfunction "P$2_2") (pintype "passive"))
    )
    (net (code "42") (name "Net-(ENC2-GND)") (class "Default")
      (node (ref "ENC2") (pin "C") (pinfunction "GND_C") (pintype "bidirectional"))
      (node (ref "R35") (pin "2") (pinfunction "P$2_2") (pintype "passive"))
    )
    (net (code "43") (name "Net-(IC1A--IN)") (class "Default")
      (node (ref "IC1") (pin "2") (pinfunction "-IN_2") (pintype "input"))
      (node (ref "R6") (pin "P$1") (pinfunction "1_P$1") (pintype "passive"))
      (node (ref "R8") (pin "1") (pinfunction "P$1_1") (pintype "passive"))
      (node (ref "TP2") (pin "P$1") (pinfunction "P$1_P$1") (pintype "bidirectional"))
    )
    (net (code "44") (name "Net-(IC1A-OUT)") (class "Default")
      (node (ref "IC1") (pin "1") (pinfunction "OUT_1") (pintype "output"))
      (node (ref "R10") (pin "2") (pinfunction "P$2_2") (pintype "passive"))
      (node (ref "R9") (pin "1") (pinfunction "P$1_1") (pintype "passive"))
    )
    (net (code "45") (name "Net-(IC1B-+IN)") (class "Default")
      (node (ref "IC1") (pin "5") (pinfunction "+IN_5") (pintype "input"))
      (node (ref "R11") (pin "1") (pinfunction "P$1_1") (pintype "passive"))
      (node (ref "R7") (pin "P$1") (pinfunction "1_P$1") (pintype "passive"))
      (node (ref "TP3") (pin "P$1") (pinfunction "P$1_P$1") (pintype "bidirectional"))
    )
    (net (code "46") (name "Net-(IC1B-OUT)") (class "Default")
      (node (ref "IC1") (pin "7") (pinfunction "OUT_7") (pintype "output"))
      (node (ref "R12") (pin "1") (pinfunction "P$1_1") (pintype "passive"))
      (node (ref "R13") (pin "2") (pinfunction "P$2_2") (pintype "passive"))
    )
    (net (code "47") (name "Net-(IC2A--IN)") (class "Default")
      (node (ref "IC2") (pin "2") (pinfunction "-IN_2") (pintype "input"))
      (node (ref "R41") (pin "P$1") (pinfunction "1_P$1") (pintype "passive"))
      (node (ref "R43") (pin "1") (pinfunction "P$1_1") (pintype "passive"))
      (node (ref "TP9") (pin "P$1") (pinfunction "P$1_P$1") (pintype "bidirectional"))
    )
    (net (code "48") (name "Net-(IC2A-OUT)") (class "Default")
      (node (ref "IC2") (pin "1") (pinfunction "OUT_1") (pintype "output"))
      (node (ref "R44") (pin "1") (pinfunction "P$1_1") (pintype "passive"))
      (node (ref "R45") (pin "2") (pinfunction "P$2_2") (pintype "passive"))
    )
    (net (code "49") (name "Net-(IC2B-+IN)") (class "Default")
      (node (ref "IC2") (pin "5") (pinfunction "+IN_5") (pintype "input"))
      (node (ref "R42") (pin "P$1") (pinfunction "1_P$1") (pintype "passive"))
      (node (ref "R46") (pin "1") (pinfunction "P$1_1") (pintype "passive"))
      (node (ref "TP10") (pin "P$1") (pinfunction "P$1_P$1") (pintype "bidirectional"))
    )
    (net (code "50") (name "Net-(IC2B-OUT)") (class "Default")
      (node (ref "IC2") (pin "7") (pinfunction "OUT_7") (pintype "output"))
      (node (ref "R47") (pin "1") (pinfunction "P$1_1") (pintype "passive"))
      (node (ref "R48") (pin "2") (pinfunction "P$2_2") (pintype "passive"))
    )
    (net (code "51") (name "Net-(IC3-VREF)") (class "Default")
      (node (ref "IC3") (pin "10") (pinfunction "VREF_10") (pintype "bidirectional"))
      (node (ref "JP14") (pin "1") (pinfunction "1_1") (pintype "passive"))
      (node (ref "TP1") (pin "P$1") (pinfunction "P$1_P$1") (pintype "bidirectional"))
    )
    (net (code "52") (name "Net-(IC7A--IN)") (class "Default")
      (node (ref "IC7") (pin "2") (pinfunction "-IN_2") (pintype "input"))
      (node (ref "R59") (pin "P$1") (pinfunction "1_P$1") (pintype "passive"))
      (node (ref "R61") (pin "1") (pinfunction "P$1_1") (pintype "passive"))
      (node (ref "TP15") (pin "P$1") (pinfunction "P$1_P$1") (pintype "bidirectional"))
    )
    (net (code "53") (name "Net-(IC7A-OUT)") (class "Default")
      (node (ref "IC7") (pin "1") (pinfunction "OUT_1") (pintype "output"))
      (node (ref "R62") (pin "1") (pinfunction "P$1_1") (pintype "passive"))
      (node (ref "R63") (pin "2") (pinfunction "P$2_2") (pintype "passive"))
    )
    (net (code "54") (name "Net-(IC7B-+IN)") (class "Default")
      (node (ref "IC7") (pin "5") (pinfunction "+IN_5") (pintype "input"))
      (node (ref "R60") (pin "P$1") (pinfunction "1_P$1") (pintype "passive"))
      (node (ref "R64") (pin "1") (pinfunction "P$1_1") (pintype "passive"))
      (node (ref "TP16") (pin "P$1") (pinfunction "P$1_P$1") (pintype "bidirectional"))
    )
    (net (code "55") (name "Net-(IC7B-OUT)") (class "Default")
      (node (ref "IC7") (pin "7") (pinfunction "OUT_7") (pintype "output"))
      (node (ref "R65") (pin "1") (pinfunction "P$1_1") (pintype "passive"))
      (node (ref "R66") (pin "2") (pinfunction "P$2_2") (pintype "passive"))
    )
    (net (code "56") (name "Net-(IC9A--IN)") (class "Default")
      (node (ref "IC9") (pin "2") (pinfunction "-IN_2") (pintype "input"))
      (node (ref "R77") (pin "P$1") (pinfunction "1_P$1") (pintype "passive"))
      (node (ref "R79") (pin "1") (pinfunction "P$1_1") (pintype "passive"))
      (node (ref "TP21") (pin "P$1") (pinfunction "P$1_P$1") (pintype "bidirectional"))
    )
    (net (code "57") (name "Net-(IC9A-OUT)") (class "Default")
      (node (ref "IC9") (pin "1") (pinfunction "OUT_1") (pintype "output"))
      (node (ref "R80") (pin "1") (pinfunction "P$1_1") (pintype "passive"))
      (node (ref "R81") (pin "2") (pinfunction "P$2_2") (pintype "passive"))
    )
    (net (code "58") (name "Net-(IC9B-+IN)") (class "Default")
      (node (ref "IC9") (pin "5") (pinfunction "+IN_5") (pintype "input"))
      (node (ref "R78") (pin "P$1") (pinfunction "1_P$1") (pintype "passive"))
      (node (ref "R82") (pin "1") (pinfunction "P$1_1") (pintype "passive"))
      (node (ref "TP22") (pin "P$1") (pinfunction "P$1_P$1") (pintype "bidirectional"))
    )
    (net (code "59") (name "Net-(IC9B-OUT)") (class "Default")
      (node (ref "IC9") (pin "7") (pinfunction "OUT_7") (pintype "output"))
      (node (ref "R83") (pin "1") (pinfunction "P$1_1") (pintype "passive"))
      (node (ref "R84") (pin "2") (pinfunction "P$2_2") (pintype "passive"))
    )
    (net (code "60") (name "Net-(LCD_HEADER-Pad1)") (class "Default")
      (node (ref "LCD_HEADER") (pin "1") (pinfunction "1_1") (pintype "passive"))
      (node (ref "U$1") (pin "3.3V") (pinfunction "3.3V_3.3V") (pintype "power_in"))
      (node (ref "U$1") (pin "3.3V1") (pinfunction "3.3V_3.3V1") (pintype "power_in"))
    )
    (net (code "61") (name "Net-(R1-P$2)") (class "Default")
      (node (ref "JP3") (pin "1") (pinfunction "1_1") (pintype "passive"))
      (node (ref "R1") (pin "2") (pinfunction "P$2_2") (pintype "passive"))
      (node (ref "R2") (pin "1") (pinfunction "P$1_1") (pintype "passive"))
      (node (ref "S1") (pin "P$3") (pinfunction "3_P$3") (pintype "bidirectional"))
    )
    (net (code "62") (name "Net-(R3-P$2)") (class "Default")
      (node (ref "JP5") (pin "1") (pinfunction "1_1") (pintype "passive"))
      (node (ref "R3") (pin "2") (pinfunction "P$2_2") (pintype "passive"))
      (node (ref "R4") (pin "1") (pinfunction "P$1_1") (pintype "passive"))
      (node (ref "S1") (pin "P$6") (pinfunction "6_P$6") (pintype "bidirectional"))
    )
    (net (code "63") (name "Net-(R5-P$1)") (class "Default")
      (node (ref "R5") (pin "1") (pinfunction "P$1_1") (pintype "passive"))
      (node (ref "S1") (pin "P$4") (pinfunction "4_P$4") (pintype "bidirectional"))
    )
    (net (code "64") (name "Net-(R5-P$2)") (class "Default")
      (node (ref "D1") (pin "C") (pinfunction "C_C") (pintype "bidirectional"))
      (node (ref "R5") (pin "2") (pinfunction "P$2_2") (pintype "passive"))
    )
    (net (code "65") (name "Net-(R10-P$1)") (class "Default")
      (node (ref "R10") (pin "1") (pinfunction "P$1_1") (pintype "passive"))
      (node (ref "T1") (pin "1") (pinfunction "B_1") (pintype "passive"))
    )
    (net (code "66") (name "Net-(R13-P$1)") (class "Default")
      (node (ref "R13") (pin "1") (pinfunction "P$1_1") (pintype "passive"))
      (node (ref "T2") (pin "1") (pinfunction "B_1") (pintype "passive"))
    )
    (net (code "67") (name "Net-(R14-P$1)") (class "Default")
      (node (ref "JP1") (pin "8") (pinfunction "8_8") (pintype "passive"))
      (node (ref "R14") (pin "1") (pinfunction "P$1_1") (pintype "passive"))
      (node (ref "R15") (pin "1") (pinfunction "P$1_1") (pintype "passive"))
    )
    (net (code "68") (name "Net-(R14-P$2)") (class "Default")
      (node (ref "R14") (pin "2") (pinfunction "P$2_2") (pintype "passive"))
      (node (ref "X1") (pin "1") (pinfunction "1_1") (pintype "passive"))
    )
    (net (code "69") (name "Net-(R18-P$2)") (class "Default")
      (node (ref "R18") (pin "2") (pinfunction "P$2_2") (pintype "passive"))
      (node (ref "X2") (pin "1") (pinfunction "1_1") (pintype "passive"))
    )
    (net (code "70") (name "Net-(R31-P$2)") (class "Default")
      (node (ref "ENC1") (pin "D") (pinfunction "D_D") (pintype "bidirectional"))
      (node (ref "R31") (pin "2") (pinfunction "P$2_2") (pintype "passive"))
    )
    (net (code "71") (name "Net-(R36-P$2)") (class "Default")
      (node (ref "ENC2") (pin "D") (pinfunction "D_D") (pintype "bidirectional"))
      (node (ref "R36") (pin "2") (pinfunction "P$2_2") (pintype "passive"))
    )
    (net (code "72") (name "Net-(R37-P$2)") (class "Default")
      (node (ref "JP6") (pin "1") (pinfunction "1_1") (pintype "passive"))
      (node (ref "R37") (pin "2") (pinfunction "P$2_2") (pintype "passive"))
      (node (ref "R38") (pin "1") (pinfunction "P$1_1") (pintype "passive"))
      (node (ref "S2") (pin "P$3") (pinfunction "3_P$3") (pintype "bidirectional"))
    )
    (net (code "73") (name "Net-(R39-P$2)") (class "Default")
      (node (ref "JP7") (pin "1") (pinfunction "1_1") (pintype "passive"))
      (node (ref "R39") (pin "2") (pinfunction "P$2_2") (pintype "passive"))
      (node (ref "R40") (pin "1") (pinfunction "P$1_1") (pintype "passive"))
      (node (ref "S2") (pin "P$6") (pinfunction "6_P$6") (pintype "bidirectional"))
    )
    (net (code "74") (name "Net-(R45-P$1)") (class "Default")
      (node (ref "R45") (pin "1") (pinfunction "P$1_1") (pintype "passive"))
      (node (ref "T3") (pin "1") (pinfunction "B_1") (pintype "passive"))
    )
    (net (code "75") (name "Net-(R48-P$1)") (class "Default")
      (node (ref "R48") (pin "1") (pinfunction "P$1_1") (pintype "passive"))
      (node (ref "T4") (pin "1") (pinfunction "B_1") (pintype "passive"))
    )
    (net (code "76") (name "Net-(R49-P$1)") (class "Default")
      (node (ref "R49") (pin "1") (pinfunction "P$1_1") (pintype "passive"))
      (node (ref "S2") (pin "P$4") (pinfunction "4_P$4") (pintype "bidirectional"))
    )
    (net (code "77") (name "Net-(R49-P$2)") (class "Default")
      (node (ref "D2") (pin "C") (pinfunction "C_C") (pintype "bidirectional"))
      (node (ref "R49") (pin "2") (pinfunction "P$2_2") (pintype "passive"))
    )
    (net (code "78") (name "Net-(R52-P$1)") (class "Default")
      (node (ref "JP2") (pin "8") (pinfunction "8_8") (pintype "passive"))
      (node (ref "R52") (pin "1") (pinfunction "P$1_1") (pintype "passive"))
      (node (ref "R53") (pin "1") (pinfunction "P$1_1") (pintype "passive"))
    )
    (net (code "79") (name "Net-(R52-P$2)") (class "Default")
      (node (ref "R52") (pin "2") (pinfunction "P$2_2") (pintype "passive"))
      (node (ref "X3") (pin "1") (pinfunction "1_1") (pintype "passive"))
    )
    (net (code "80") (name "Net-(R54-P$2)") (class "Default")
      (node (ref "R54") (pin "2") (pinfunction "P$2_2") (pintype "passive"))
      (node (ref "X4") (pin "1") (pinfunction "1_1") (pintype "passive"))
    )
    (net (code "81") (name "Net-(R55-P$2)") (class "Default")
      (node (ref "JP9") (pin "1") (pinfunction "1_1") (pintype "passive"))
      (node (ref "R55") (pin "2") (pinfunction "P$2_2") (pintype "passive"))
      (node (ref "R56") (pin "1") (pinfunction "P$1_1") (pintype "passive"))
      (node (ref "S3") (pin "P$3") (pinfunction "3_P$3") (pintype "bidirectional"))
    )
    (net (code "82") (name "Net-(R57-P$2)") (class "Default")
      (node (ref "JP10") (pin "1") (pinfunction "1_1") (pintype "passive"))
      (node (ref "R57") (pin "2") (pinfunction "P$2_2") (pintype "passive"))
      (node (ref "R58") (pin "1") (pinfunction "P$1_1") (pintype "passive"))
      (node (ref "S3") (pin "P$6") (pinfunction "6_P$6") (pintype "bidirectional"))
    )
    (net (code "83") (name "Net-(R63-P$1)") (class "Default")
      (node (ref "R63") (pin "1") (pinfunction "P$1_1") (pintype "passive"))
      (node (ref "T5") (pin "1") (pinfunction "B_1") (pintype "passive"))
    )
    (net (code "84") (name "Net-(R66-P$1)") (class "Default")
      (node (ref "R66") (pin "1") (pinfunction "P$1_1") (pintype "passive"))
      (node (ref "T6") (pin "1") (pinfunction "B_1") (pintype "passive"))
    )
    (net (code "85") (name "Net-(R67-P$1)") (class "Default")
      (node (ref "R67") (pin "1") (pinfunction "P$1_1") (pintype "passive"))
      (node (ref "S3") (pin "P$4") (pinfunction "4_P$4") (pintype "bidirectional"))
    )
    (net (code "86") (name "Net-(R67-P$2)") (class "Default")
      (node (ref "D3") (pin "C") (pinfunction "C_C") (pintype "bidirectional"))
      (node (ref "R67") (pin "2") (pinfunction "P$2_2") (pintype "passive"))
    )
    (net (code "87") (name "Net-(R70-P$1)") (class "Default")
      (node (ref "JP8") (pin "8") (pinfunction "8_8") (pintype "passive"))
      (node (ref "R70") (pin "1") (pinfunction "P$1_1") (pintype "passive"))
      (node (ref "R71") (pin "1") (pinfunction "P$1_1") (pintype "passive"))
    )
    (net (code "88") (name "Net-(R70-P$2)") (class "Default")
      (node (ref "R70") (pin "2") (pinfunction "P$2_2") (pintype "passive"))
      (node (ref "X5") (pin "1") (pinfunction "1_1") (pintype "passive"))
    )
    (net (code "89") (name "Net-(R72-P$2)") (class "Default")
      (node (ref "R72") (pin "2") (pinfunction "P$2_2") (pintype "passive"))
      (node (ref "X6") (pin "1") (pinfunction "1_1") (pintype "passive"))
    )
    (net (code "90") (name "Net-(R73-P$2)") (class "Default")
      (node (ref "JP12") (pin "1") (pinfunction "1_1") (pintype "passive"))
      (node (ref "R73") (pin "2") (pinfunction "P$2_2") (pintype "passive"))
      (node (ref "R74") (pin "1") (pinfunction "P$1_1") (pintype "passive"))
      (node (ref "S4") (pin "P$3") (pinfunction "3_P$3") (pintype "bidirectional"))
    )
    (net (code "91") (name "Net-(R75-P$2)") (class "Default")
      (node (ref "JP13") (pin "1") (pinfunction "1_1") (pintype "passive"))
      (node (ref "R75") (pin "2") (pinfunction "P$2_2") (pintype "passive"))
      (node (ref "R76") (pin "1") (pinfunction "P$1_1") (pintype "passive"))
      (node (ref "S4") (pin "P$6") (pinfunction "6_P$6") (pintype "bidirectional"))
    )
    (net (code "92") (name "Net-(R81-P$1)") (class "Default")
      (node (ref "R81") (pin "1") (pinfunction "P$1_1") (pintype "passive"))
      (node (ref "T7") (pin "1") (pinfunction "B_1") (pintype "passive"))
    )
    (net (code "93") (name "Net-(R84-P$1)") (class "Default")
      (node (ref "R84") (pin "1") (pinfunction "P$1_1") (pintype "passive"))
      (node (ref "T8") (pin "1") (pinfunction "B_1") (pintype "passive"))
    )
    (net (code "94") (name "Net-(R85-P$1)") (class "Default")
      (node (ref "R85") (pin "1") (pinfunction "P$1_1") (pintype "passive"))
      (node (ref "S4") (pin "P$4") (pinfunction "4_P$4") (pintype "bidirectional"))
    )
    (net (code "95") (name "Net-(R85-P$2)") (class "Default")
      (node (ref "D4") (pin "C") (pinfunction "C_C") (pintype "bidirectional"))
      (node (ref "R85") (pin "2") (pinfunction "P$2_2") (pintype "passive"))
    )
    (net (code "96") (name "Net-(R88-P$1)") (class "Default")
      (node (ref "JP11") (pin "8") (pinfunction "8_8") (pintype "passive"))
      (node (ref "R88") (pin "1") (pinfunction "P$1_1") (pintype "passive"))
      (node (ref "R89") (pin "1") (pinfunction "P$1_1") (pintype "passive"))
    )
    (net (code "97") (name "Net-(R88-P$2)") (class "Default")
      (node (ref "R88") (pin "2") (pinfunction "P$2_2") (pintype "passive"))
      (node (ref "X7") (pin "1") (pinfunction "1_1") (pintype "passive"))
    )
    (net (code "98") (name "Net-(R90-P$2)") (class "Default")
      (node (ref "R90") (pin "2") (pinfunction "P$2_2") (pintype "passive"))
      (node (ref "X8") (pin "1") (pinfunction "1_1") (pintype "passive"))
    )
    (net (code "99") (name "P1") (class "Default")
      (node (ref "IC4") (pin "2") (pinfunction "A1_2") (pintype "bidirectional"))
      (node (ref "JP1") (pin "1") (pinfunction "1_1") (pintype "passive"))
      (node (ref "TP4") (pin "P$1") (pinfunction "P$1_P$1") (pintype "bidirectional"))
    )
    (net (code "100") (name "P2") (class "Default")
      (node (ref "IC5") (pin "2") (pinfunction "A1_2") (pintype "bidirectional"))
      (node (ref "JP2") (pin "1") (pinfunction "1_1") (pintype "passive"))
      (node (ref "TP11") (pin "P$1") (pinfunction "P$1_P$1") (pintype "bidirectional"))
    )
    (net (code "101") (name "P3") (class "Default")
      (node (ref "IC8") (pin "2") (pinfunction "A1_2") (pintype "bidirectional"))
      (node (ref "JP8") (pin "1") (pinfunction "1_1") (pintype "passive"))
      (node (ref "TP17") (pin "P$1") (pinfunction "P$1_P$1") (pintype "bidirectional"))
    )
    (net (code "102") (name "P4") (class "Default")
      (node (ref "IC10") (pin "2") (pinfunction "A1_2") (pintype "bidirectional"))
      (node (ref "JP11") (pin "1") (pinfunction "1_1") (pintype "passive"))
      (node (ref "TP23") (pin "P$1") (pinfunction "P$1_P$1") (pintype "bidirectional"))
    )
    (net (code "103") (name "RST_LCD") (class "Default")
      (node (ref "LCD_HEADER") (pin "8") (pinfunction "8_8") (pintype "passive"))
      (node (ref "U$1") (pin "9") (pinfunction "9/RX2/PWM_9") (pintype "bidirectional"))
    )
    (net (code "104") (name "RS_LCD") (class "Default")
      (node (ref "LCD_HEADER") (pin "7") (pinfunction "7_7") (pintype "passive"))
      (node (ref "U$1") (pin "10") (pinfunction "10/TX2/PWM_10") (pintype "bidirectional"))
    )
    (net (code "105") (name "SCK") (class "Default")
      (node (ref "LCD_HEADER") (pin "5") (pinfunction "5_5") (pintype "passive"))
      (node (ref "U$1") (pin "13") (pinfunction "13/SCK/LED_13") (pintype "bidirectional"))
    )
    (net (code "106") (name "SCK_B") (class "Default")
      (node (ref "IC10") (pin "7") (pinfunction "CLK_7") (pintype "bidirectional"))
      (node (ref "IC3") (pin "7") (pinfunction "SCLK_7") (pintype "bidirectional"))
      (node (ref "IC4") (pin "7") (pinfunction "CLK_7") (pintype "bidirectional"))
      (node (ref "IC5") (pin "7") (pinfunction "CLK_7") (pintype "bidirectional"))
      (node (ref "IC8") (pin "7") (pinfunction "CLK_7") (pintype "bidirectional"))
      (node (ref "U$1") (pin "1") (pinfunction "1/TX1/T_1") (pintype "bidirectional"))
    )
    (net (code "107") (name "VBAT") (class "Default")
      (node (ref "U$1") (pin "VBAT") (pinfunction "VBAT_VBAT") (pintype "power_in"))
    )
    (net (code "108") (name "VDD") (class "Default")
      (node (ref "C12") (pin "2") (pinfunction "P$2_2") (pintype "passive"))
      (node (ref "C13") (pin "2") (pinfunction "P$2_2") (pintype "passive"))
      (node (ref "C15") (pin "2") (pinfunction "P$2_2") (pintype "passive"))
      (node (ref "C20") (pin "2") (pinfunction "P$2_2") (pintype "passive"))
      (node (ref "C21") (pin "2") (pinfunction "P$2_2") (pintype "passive"))
      (node (ref "C22") (pin "2") (pinfunction "P$2_2") (pintype "passive"))
      (node (ref "C23") (pin "2") (pinfunction "P$2_2") (pintype "passive"))
      (node (ref "C24") (pin "2") (pinfunction "P$2_2") (pintype "passive"))
      (node (ref "C25") (pin "2") (pinfunction "P$2_2") (pintype "passive"))
      (node (ref "CP3") (pin "+") (pinfunction "+_+") (pintype "passive"))
      (node (ref "D1") (pin "A") (pinfunction "A_A") (pintype "bidirectional"))
      (node (ref "D2") (pin "A") (pinfunction "A_A") (pintype "bidirectional"))
      (node (ref "D3") (pin "A") (pinfunction "A_A") (pintype "bidirectional"))
      (node (ref "D4") (pin "A") (pinfunction "A_A") (pintype "bidirectional"))
      (node (ref "IC1") (pin "8") (pinfunction "V+_8") (pintype "power_in"))
      (node (ref "IC10") (pin "10") (pinfunction "PR_10") (pintype "bidirectional"))
      (node (ref "IC10") (pin "13") (pinfunction "VL_13") (pintype "power_in"))
      (node (ref "IC10") (pin "5") (pinfunction "VDD_5") (pintype "power_in"))
      (node (ref "IC10") (pin "6") (pinfunction "SHDN_6") (pintype "bidirectional"))
      (node (ref "IC2") (pin "8") (pinfunction "V+_8") (pintype "power_in"))
      (node (ref "IC4") (pin "10") (pinfunction "PR_10") (pintype "bidirectional"))
      (node (ref "IC4") (pin "13") (pinfunction "VL_13") (pintype "power_in"))
      (node (ref "IC4") (pin "5") (pinfunction "VDD_5") (pintype "power_in"))
      (node (ref "IC4") (pin "6") (pinfunction "SHDN_6") (pintype "bidirectional"))
      (node (ref "IC5") (pin "10") (pinfunction "PR_10") (pintype "bidirectional"))
      (node (ref "IC5") (pin "13") (pinfunction "VL_13") (pintype "power_in"))
      (node (ref "IC5") (pin "5") (pinfunction "VDD_5") (pintype "power_in"))
      (node (ref "IC5") (pin "6") (pinfunction "SHDN_6") (pintype "bidirectional"))
      (node (ref "IC6") (pin "1") (pinfunction "IN_1") (pintype "bidirectional"))
      (node (ref "IC7") (pin "8") (pinfunction "V+_8") (pintype "power_in"))
      (node (ref "IC8") (pin "10") (pinfunction "PR_10") (pintype "bidirectional"))
      (node (ref "IC8") (pin "13") (pinfunction "VL_13") (pintype "power_in"))
      (node (ref "IC8") (pin "5") (pinfunction "VDD_5") (pintype "power_in"))
      (node (ref "IC8") (pin "6") (pinfunction "SHDN_6") (pintype "bidirectional"))
      (node (ref "IC9") (pin "8") (pinfunction "V+_8") (pintype "power_in"))
      (node (ref "JP1") (pin "11") (pinfunction "11_11") (pintype "passive"))
      (node (ref "JP1") (pin "2") (pinfunction "2_2") (pintype "passive"))
      (node (ref "JP11") (pin "11") (pinfunction "11_11") (pintype "passive"))
      (node (ref "JP11") (pin "2") (pinfunction "2_2") (pintype "passive"))
      (node (ref "JP2") (pin "11") (pinfunction "11_11") (pintype "passive"))
      (node (ref "JP2") (pin "2") (pinfunction "2_2") (pintype "passive"))
      (node (ref "JP8") (pin "11") (pinfunction "11_11") (pintype "passive"))
      (node (ref "JP8") (pin "2") (pinfunction "2_2") (pintype "passive"))
      (node (ref "L1") (pin "2") (pinfunction "P$2_2") (pintype "passive"))
      (node (ref "L2") (pin "2") (pinfunction "P$2_2") (pintype "passive"))
      (node (ref "L4") (pin "1") (pinfunction "P$1_1") (pintype "passive"))
      (node (ref "R11") (pin "2") (pinfunction "P$2_2") (pintype "passive"))
      (node (ref "R12") (pin "2") (pinfunction "P$2_2") (pintype "passive"))
      (node (ref "R19") (pin "2") (pinfunction "P$2_2") (pintype "passive"))
      (node (ref "R28") (pin "P$2") (pinfunction "2_P$2") (pintype "passive"))
      (node (ref "R29") (pin "2") (pinfunction "P$2_2") (pintype "passive"))
      (node (ref "R32") (pin "2") (pinfunction "P$2_2") (pintype "passive"))
      (node (ref "R33") (pin "P$2") (pinfunction "2_P$2") (pintype "passive"))
      (node (ref "R34") (pin "2") (pinfunction "P$2_2") (pintype "passive"))
      (node (ref "R43") (pin "2") (pinfunction "P$2_2") (pintype "passive"))
      (node (ref "R44") (pin "2") (pinfunction "P$2_2") (pintype "passive"))
      (node (ref "R46") (pin "2") (pinfunction "P$2_2") (pintype "passive"))
      (node (ref "R47") (pin "2") (pinfunction "P$2_2") (pintype "passive"))
      (node (ref "R61") (pin "2") (pinfunction "P$2_2") (pintype "passive"))
      (node (ref "R62") (pin "2") (pinfunction "P$2_2") (pintype "passive"))
      (node (ref "R64") (pin "2") (pinfunction "P$2_2") (pintype "passive"))
      (node (ref "R65") (pin "2") (pinfunction "P$2_2") (pintype "passive"))
      (node (ref "R79") (pin "2") (pinfunction "P$2_2") (pintype "passive"))
      (node (ref "R8") (pin "2") (pinfunction "P$2_2") (pintype "passive"))
      (node (ref "R80") (pin "2") (pinfunction "P$2_2") (pintype "passive"))
      (node (ref "R82") (pin "2") (pinfunction "P$2_2") (pintype "passive"))
      (node (ref "R83") (pin "2") (pinfunction "P$2_2") (pintype "passive"))
      (node (ref "R9") (pin "2") (pinfunction "P$2_2") (pintype "passive"))
    )
    (net (code "109") (name "VMON1") (class "Default")
      (node (ref "JP1") (pin "7") (pinfunction "7_7") (pintype "passive"))
      (node (ref "R18") (pin "1") (pinfunction "P$1_1") (pintype "passive"))
      (node (ref "R26") (pin "P$2") (pinfunction "2_P$2") (pintype "passive"))
    )
    (net (code "110") (name "VMON1_B") (class "Default")
      (node (ref "C9") (pin "2") (pinfunction "P$2_2") (pintype "passive"))
      (node (ref "R26") (pin "P$1") (pinfunction "1_P$1") (pintype "passive"))
      (node (ref "R27") (pin "P$2") (pinfunction "2_P$2") (pintype "passive"))
      (node (ref "U$1") (pin "A10") (pinfunction "A10_A10") (pintype "bidirectional"))
    )
    (net (code "111") (name "VMON2") (class "Default")
      (node (ref "JP2") (pin "7") (pinfunction "7_7") (pintype "passive"))
      (node (ref "R24") (pin "P$2") (pinfunction "2_P$2") (pintype "passive"))
      (node (ref "R54") (pin "1") (pinfunction "P$1_1") (pintype "passive"))
    )
    (net (code "112") (name "VMON2_B") (class "Default")
      (node (ref "C6") (pin "2") (pinfunction "P$2_2") (pintype "passive"))
      (node (ref "R24") (pin "P$1") (pinfunction "1_P$1") (pintype "passive"))
      (node (ref "R25") (pin "P$2") (pinfunction "2_P$2") (pintype "passive"))
      (node (ref "U$1") (pin "22/A8") (pinfunction "22/A8/T/PWM_22/A8") (pintype "bidirectional"))
    )
    (net (code "113") (name "VMON3") (class "Default")
      (node (ref "JP8") (pin "7") (pinfunction "7_7") (pintype "passive"))
      (node (ref "R22") (pin "P$2") (pinfunction "2_P$2") (pintype "passive"))
      (node (ref "R72") (pin "1") (pinfunction "P$1_1") (pintype "passive"))
    )
    (net (code "114") (name "VMON3_B") (class "Default")
      (node (ref "C4") (pin "2") (pinfunction "P$2_2") (pintype "passive"))
      (node (ref "R22") (pin "P$1") (pinfunction "1_P$1") (pintype "passive"))
      (node (ref "R23") (pin "P$2") (pinfunction "2_P$2") (pintype "passive"))
      (node (ref "U$1") (pin "20/A6") (pinfunction "20/A6/PWM_20/A6") (pintype "bidirectional"))
    )
    (net (code "115") (name "VMON4") (class "Default")
      (node (ref "JP11") (pin "7") (pinfunction "7_7") (pintype "passive"))
      (node (ref "R20") (pin "P$2") (pinfunction "2_P$2") (pintype "passive"))
      (node (ref "R90") (pin "1") (pinfunction "P$1_1") (pintype "passive"))
    )
    (net (code "116") (name "VMON4_B") (class "Default")
      (node (ref "C3") (pin "2") (pinfunction "P$2_2") (pintype "passive"))
      (node (ref "R20") (pin "P$1") (pinfunction "1_P$1") (pintype "passive"))
      (node (ref "R21") (pin "P$2") (pinfunction "2_P$2") (pintype "passive"))
      (node (ref "U$1") (pin "18/A4") (pinfunction "18/A4/T/SDA0_18/A4") (pintype "bidirectional"))
    )
    (net (code "117") (name "VSET1") (class "Default")
      (node (ref "IC1") (pin "3") (pinfunction "+IN_3") (pintype "input"))
      (node (ref "IC1") (pin "6") (pinfunction "-IN_6") (pintype "input"))
      (node (ref "IC3") (pin "1") (pinfunction "VOUTA_1") (pintype "output"))
      (node (ref "JP1") (pin "10") (pinfunction "10_10") (pintype "passive"))
      (node (ref "TP8") (pin "P$1") (pinfunction "P$1_P$1") (pintype "bidirectional"))
    )
    (net (code "118") (name "VSET2") (class "Default")
      (node (ref "IC2") (pin "3") (pinfunction "+IN_3") (pintype "input"))
      (node (ref "IC2") (pin "6") (pinfunction "-IN_6") (pintype "input"))
      (node (ref "IC3") (pin "2") (pinfunction "VOUTB_2") (pintype "output"))
      (node (ref "JP2") (pin "10") (pinfunction "10_10") (pintype "passive"))
      (node (ref "TP14") (pin "P$1") (pinfunction "P$1_P$1") (pintype "bidirectional"))
    )
    (net (code "119") (name "VSET3") (class "Default")
      (node (ref "IC3") (pin "4") (pinfunction "VOUTC_4") (pintype "output"))
      (node (ref "IC7") (pin "3") (pinfunction "+IN_3") (pintype "input"))
      (node (ref "IC7") (pin "6") (pinfunction "-IN_6") (pintype "input"))
      (node (ref "JP8") (pin "10") (pinfunction "10_10") (pintype "passive"))
      (node (ref "TP20") (pin "P$1") (pinfunction "P$1_P$1") (pintype "bidirectional"))
    )
    (net (code "120") (name "VSET4") (class "Default")
      (node (ref "IC3") (pin "5") (pinfunction "VOUTD_5") (pintype "output"))
      (node (ref "IC9") (pin "3") (pinfunction "+IN_3") (pintype "input"))
      (node (ref "IC9") (pin "6") (pinfunction "-IN_6") (pintype "input"))
      (node (ref "JP11") (pin "10") (pinfunction "10_10") (pintype "passive"))
      (node (ref "TP26") (pin "P$1") (pinfunction "P$1_P$1") (pintype "bidirectional"))
    )
    (net (code "121") (name "VUSB") (class "Default")
      (node (ref "U$1") (pin "VUSB") (pinfunction "VUSB_VUSB") (pintype "power_in"))
    )
    (net (code "122") (name "unconnected-(IC4-SDO-Pad1)") (class "Default")
      (node (ref "IC4") (pin "1") (pinfunction "SDO_1") (pintype "bidirectional"))
    )
    (net (code "123") (name "unconnected-(IC5-SDO-Pad1)") (class "Default")
      (node (ref "IC5") (pin "1") (pinfunction "SDO_1") (pintype "bidirectional"))
    )
    (net (code "124") (name "unconnected-(IC8-SDO-Pad1)") (class "Default")
      (node (ref "IC8") (pin "1") (pinfunction "SDO_1") (pintype "bidirectional"))
    )
    (net (code "125") (name "unconnected-(IC10-SDO-Pad1)") (class "Default")
      (node (ref "IC10") (pin "1") (pinfunction "SDO_1") (pintype "bidirectional"))
    )
    (net (code "126") (name "unconnected-(S1-1-PadP$1)") (class "Default")
      (node (ref "S1") (pin "P$1") (pinfunction "1_P$1") (pintype "bidirectional"))
    )
    (net (code "127") (name "unconnected-(S2-1-PadP$1)") (class "Default")
      (node (ref "S2") (pin "P$1") (pinfunction "1_P$1") (pintype "bidirectional"))
    )
    (net (code "128") (name "unconnected-(S3-1-PadP$1)") (class "Default")
      (node (ref "S3") (pin "P$1") (pinfunction "1_P$1") (pintype "bidirectional"))
    )
    (net (code "129") (name "unconnected-(S4-1-PadP$1)") (class "Default")
      (node (ref "S4") (pin "P$1") (pinfunction "1_P$1") (pintype "bidirectional"))
    )
    (net (code "130") (name "unconnected-(U$1-A14{slash}DAC-PadA14)") (class "Default")
      (node (ref "U$1") (pin "A14") (pinfunction "A14/DAC_A14") (pintype "bidirectional"))
    )
    (net (code "131") (name "unconnected-(U$1-PadPGM)") (class "Default")
      (node (ref "U$1") (pin "PGM") (pinfunction "PGM_PGM") (pintype "bidirectional"))
    )
  )
)
